# Versie_4.net
KiCad netlist of a schematic drawn in EAGLE
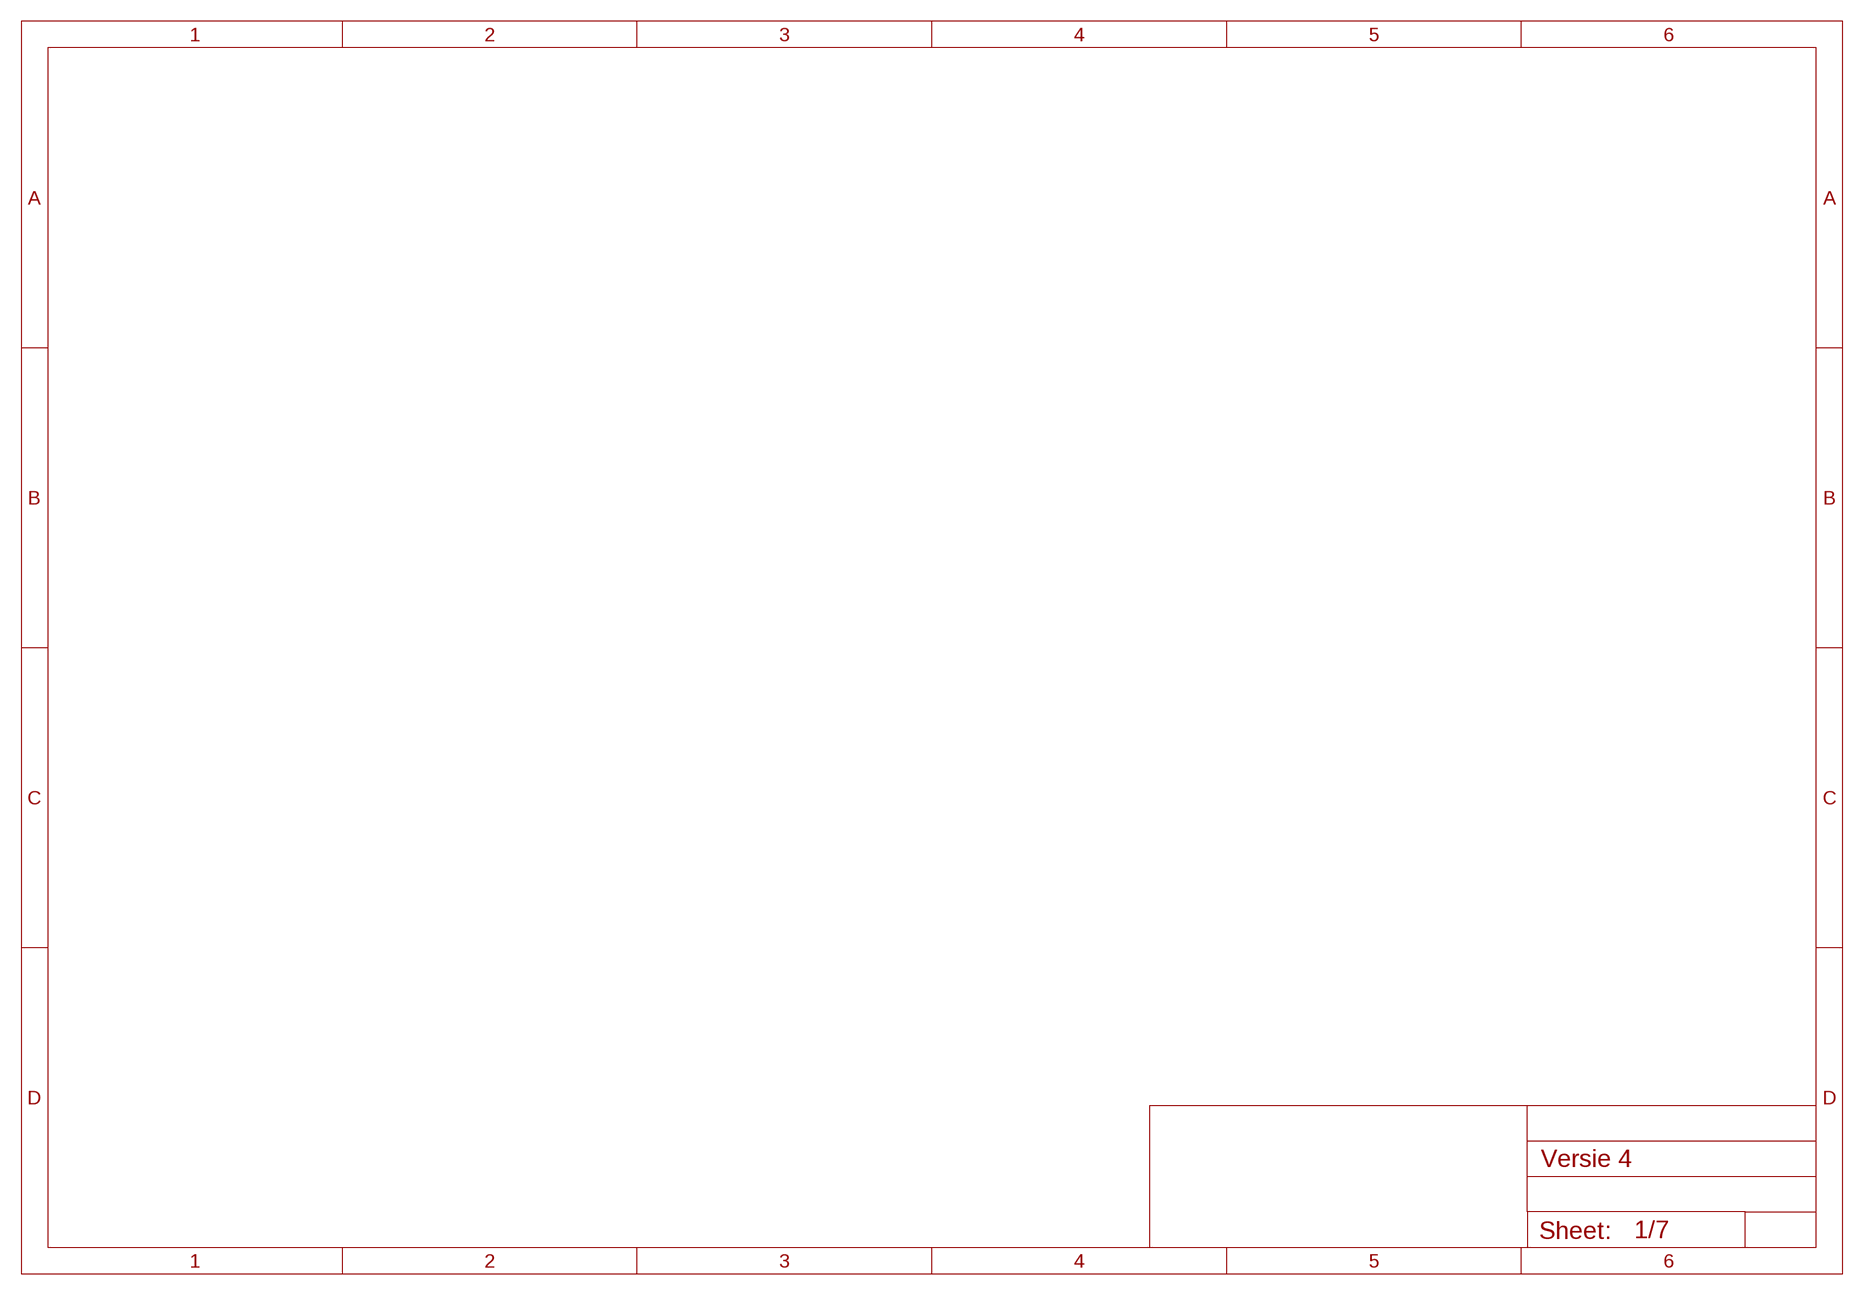
[diagram p0: schematic, sheet 1]
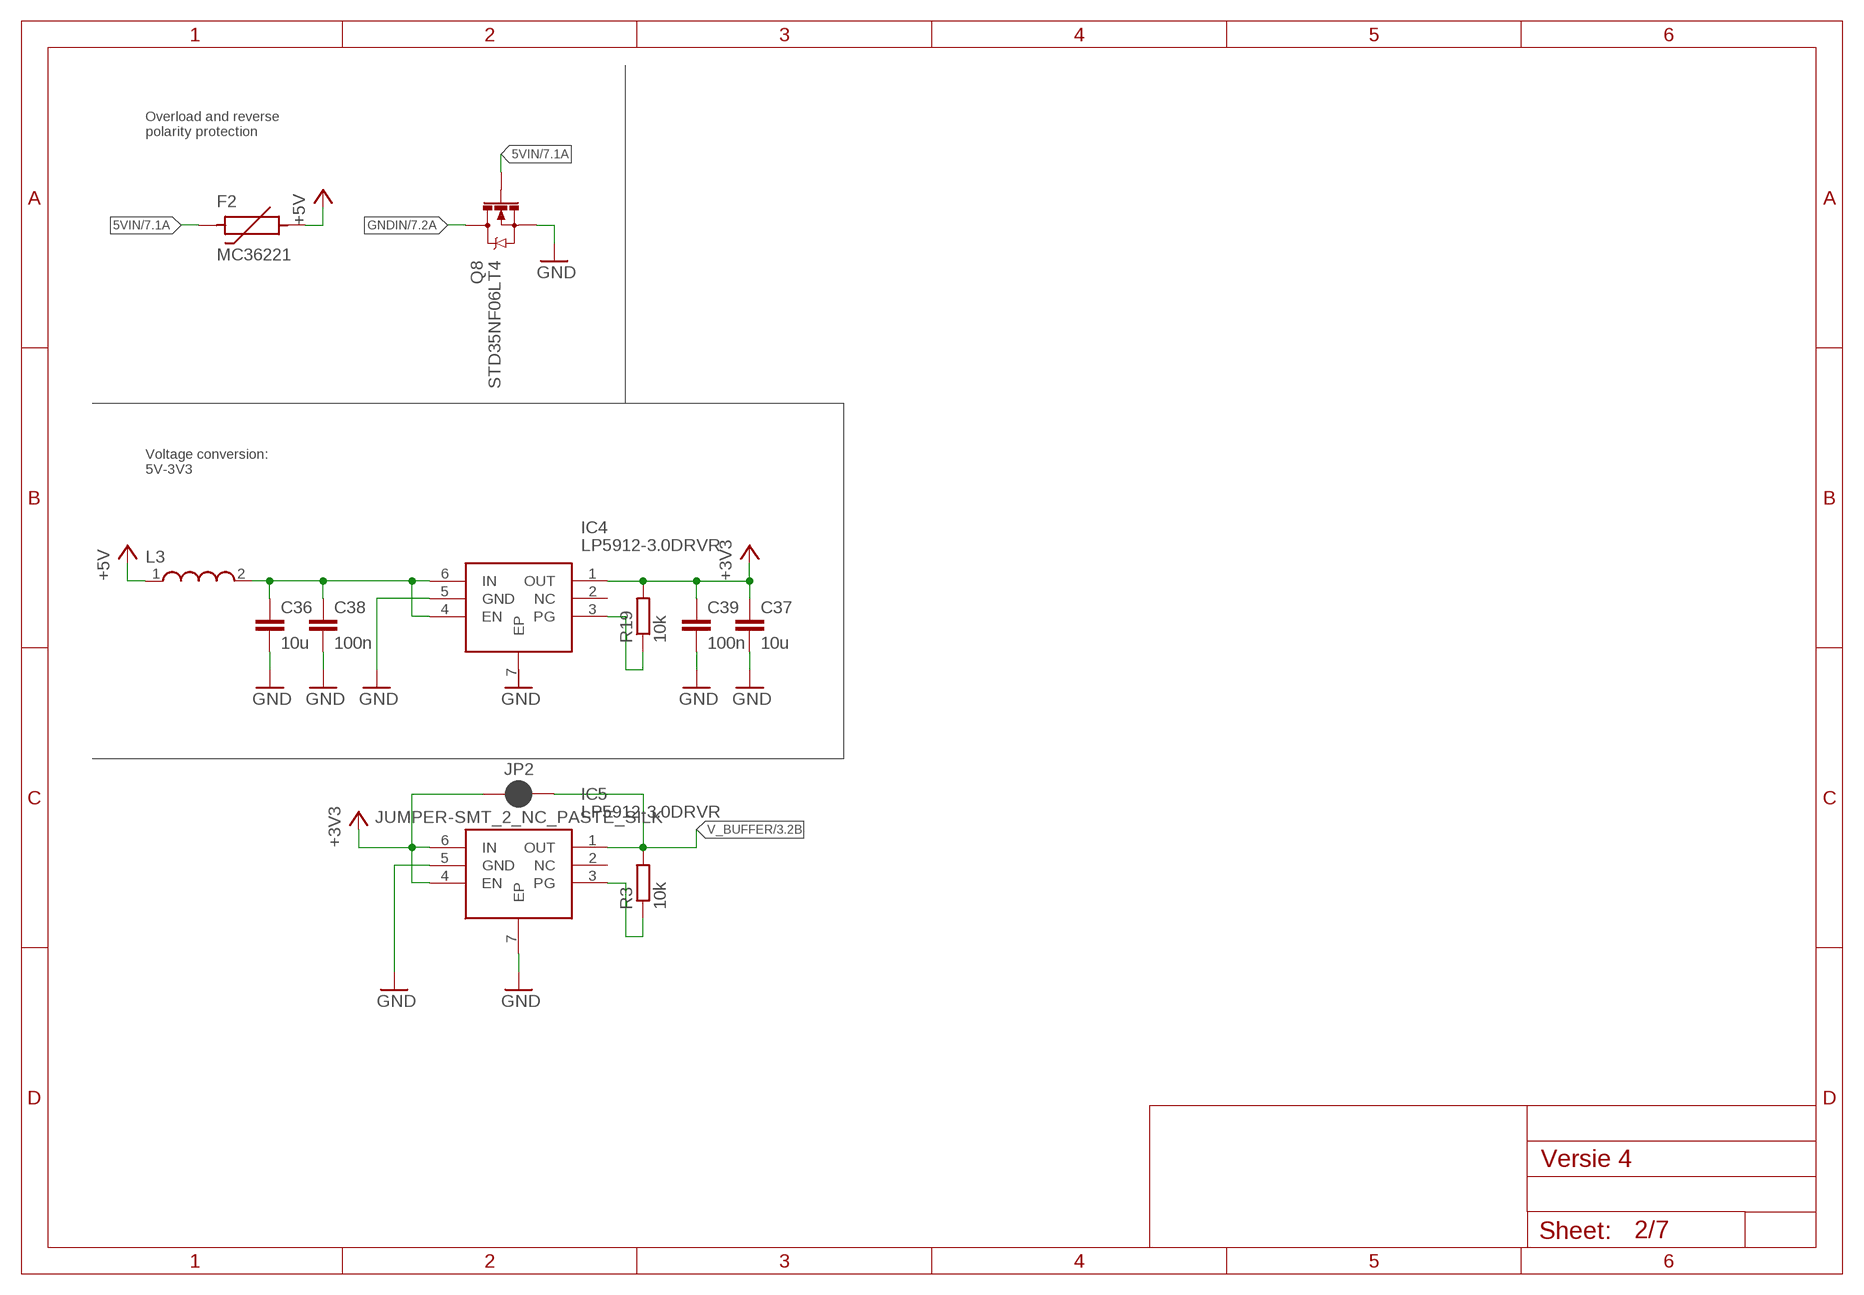
[diagram p1: schematic, sheet 2]
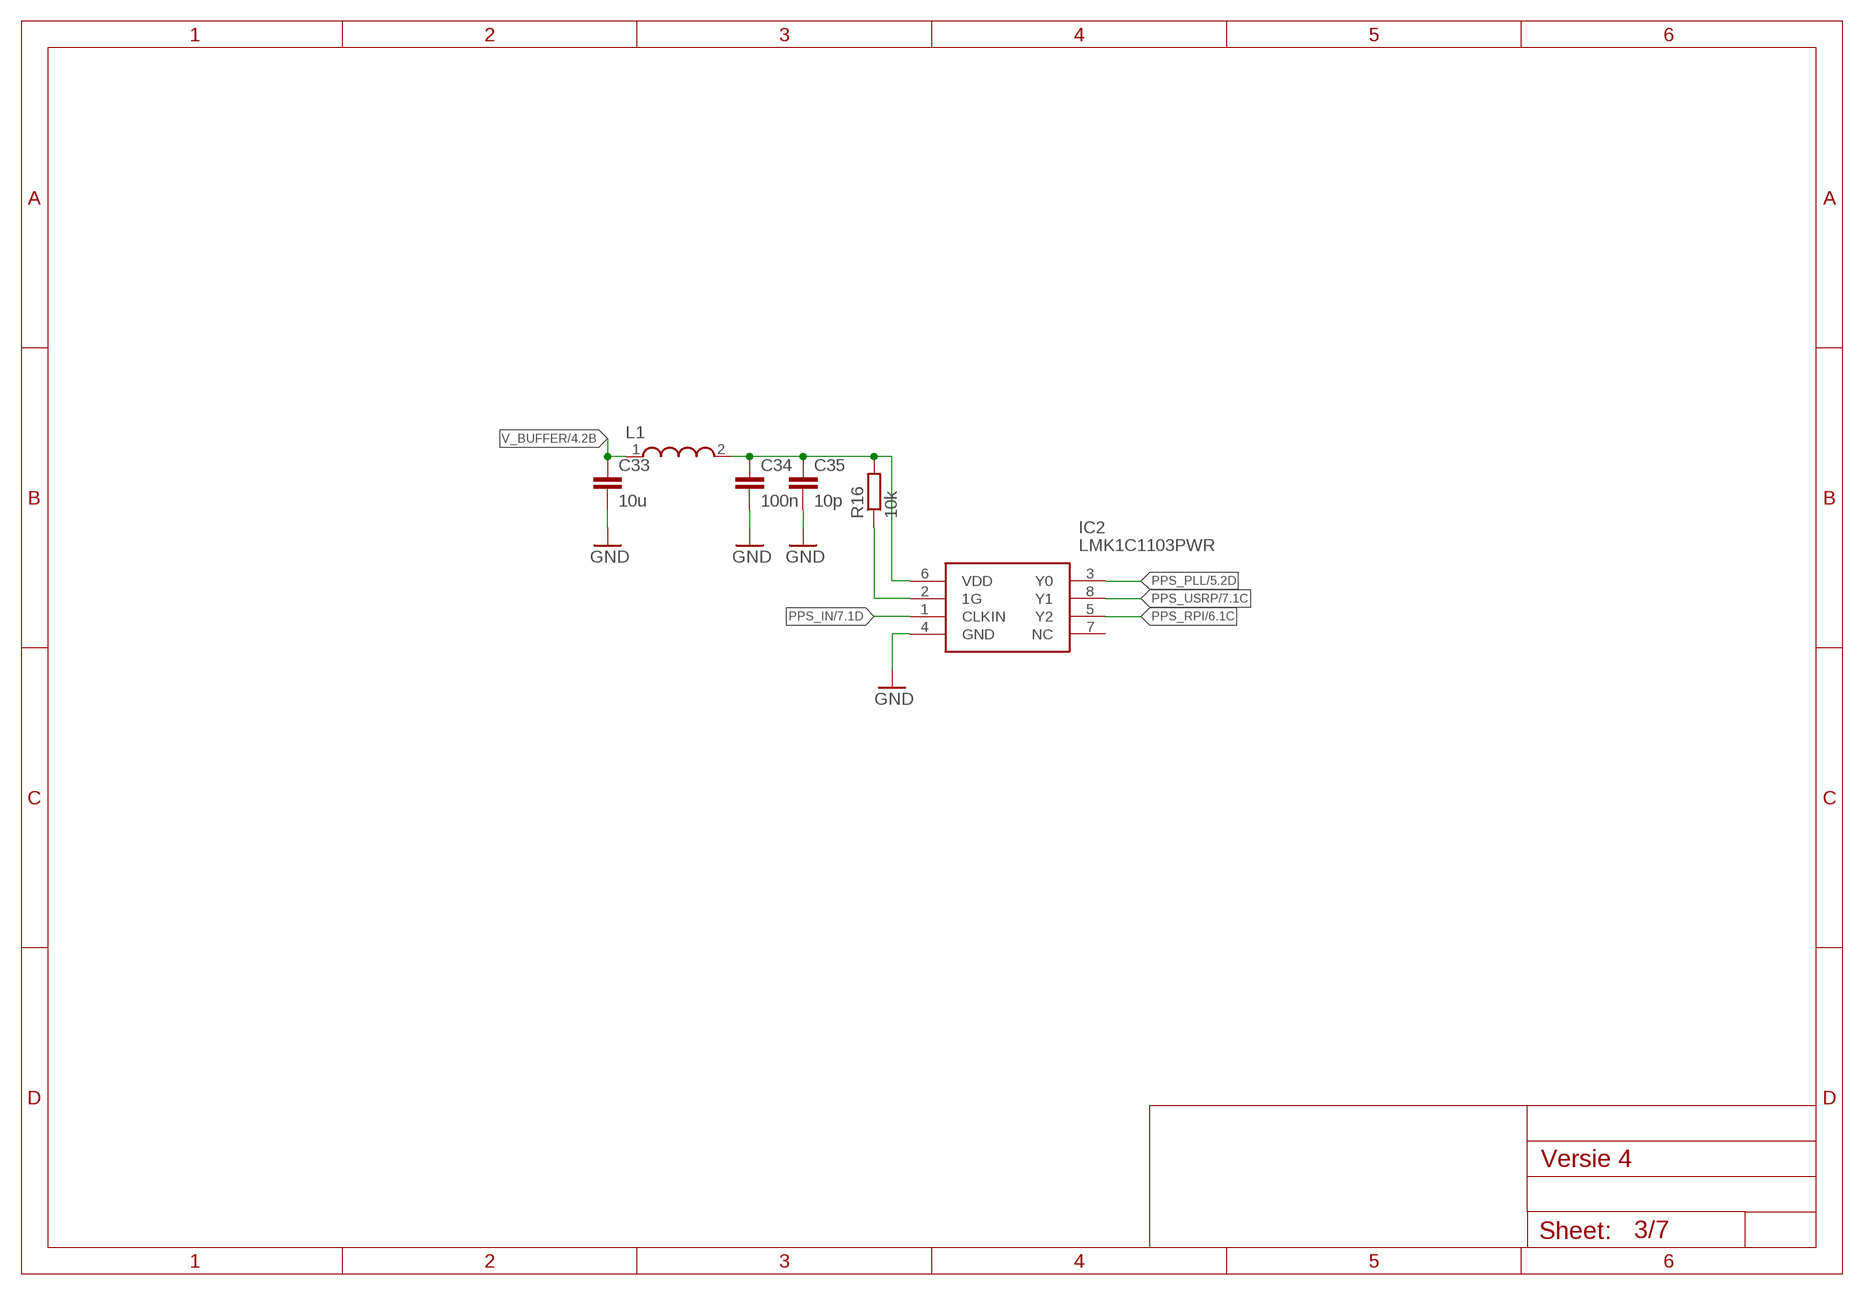
[diagram p2: schematic, sheet 3]
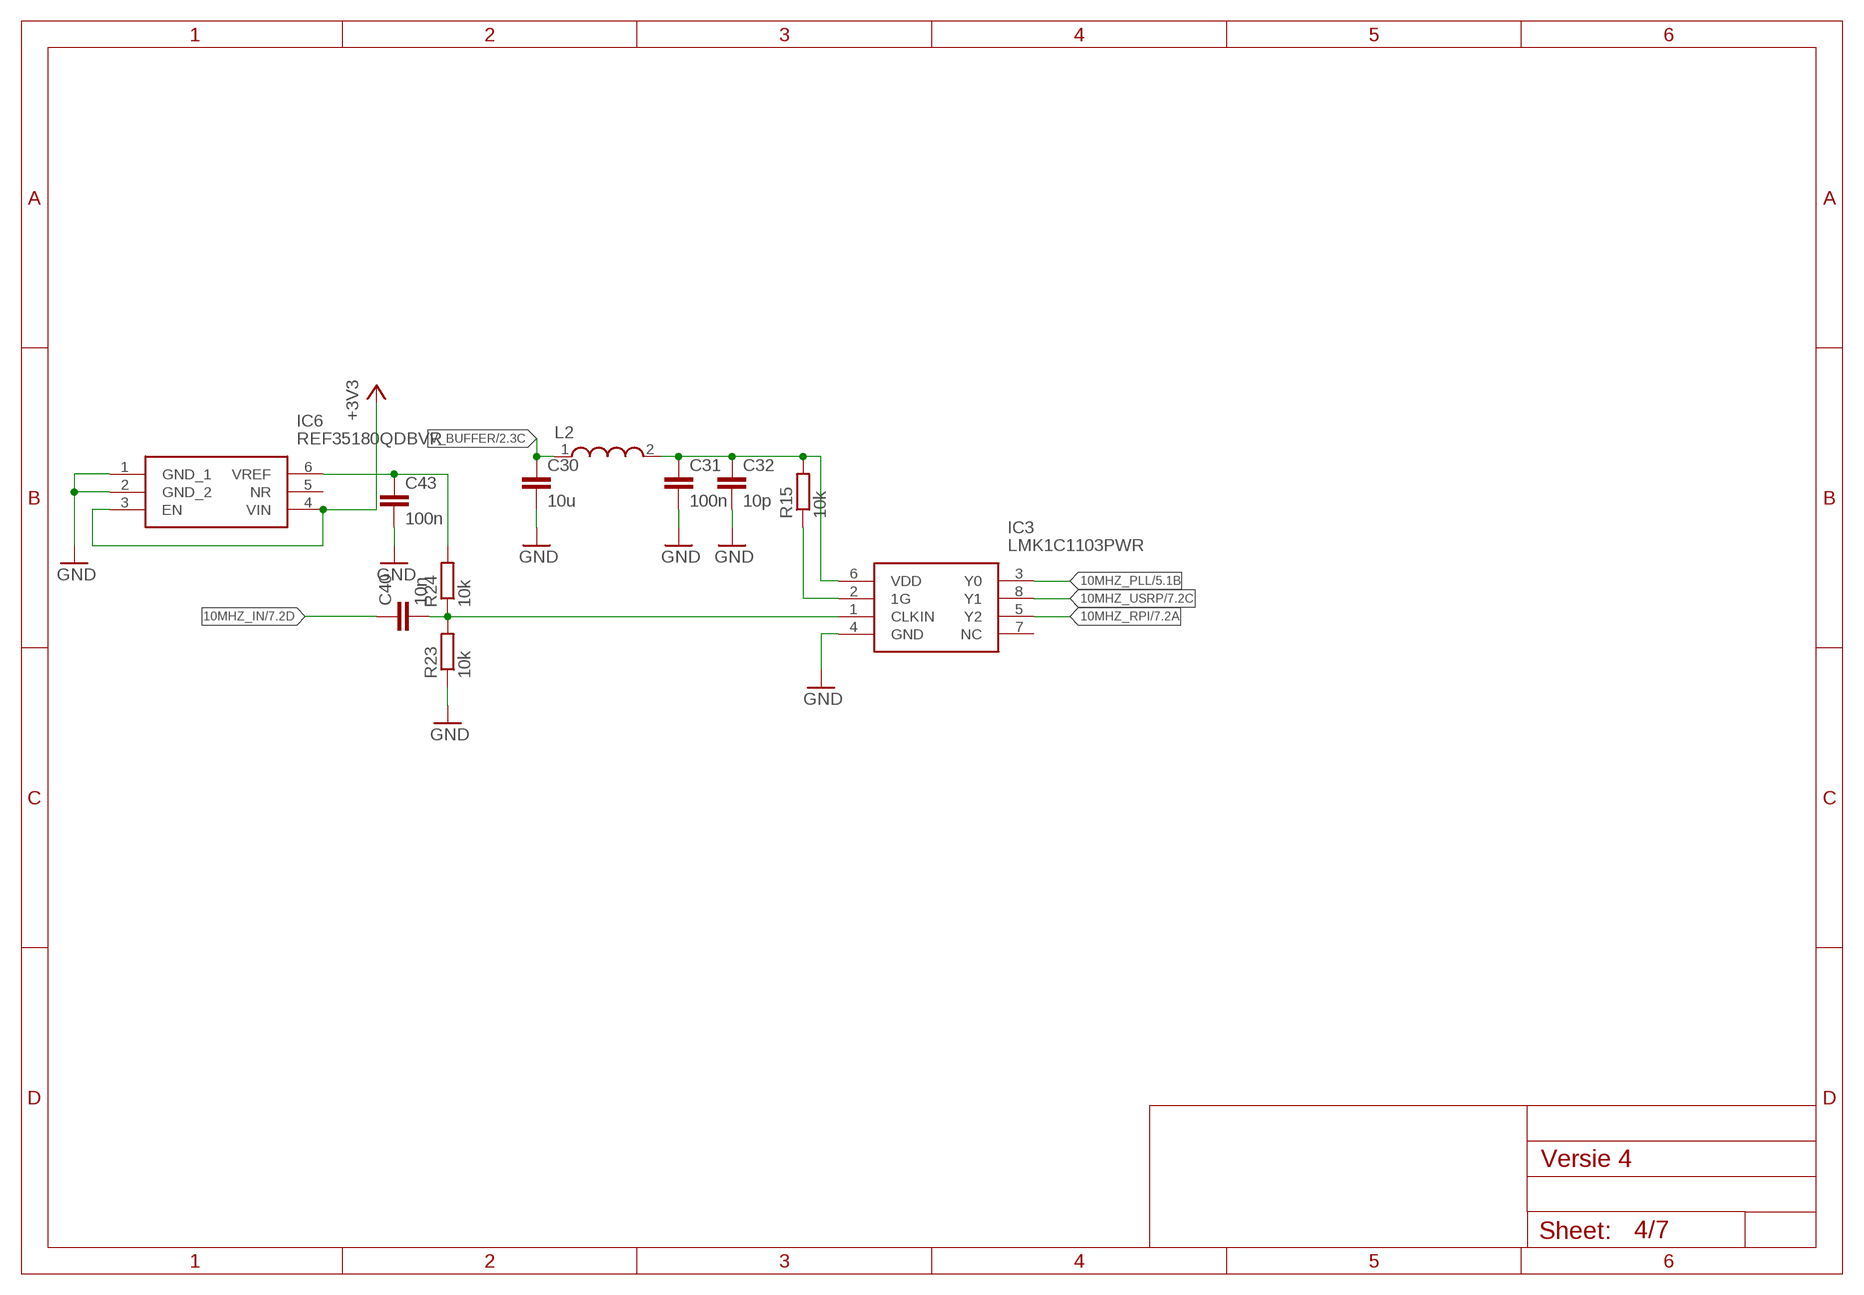
[diagram p3: schematic, sheet 4]
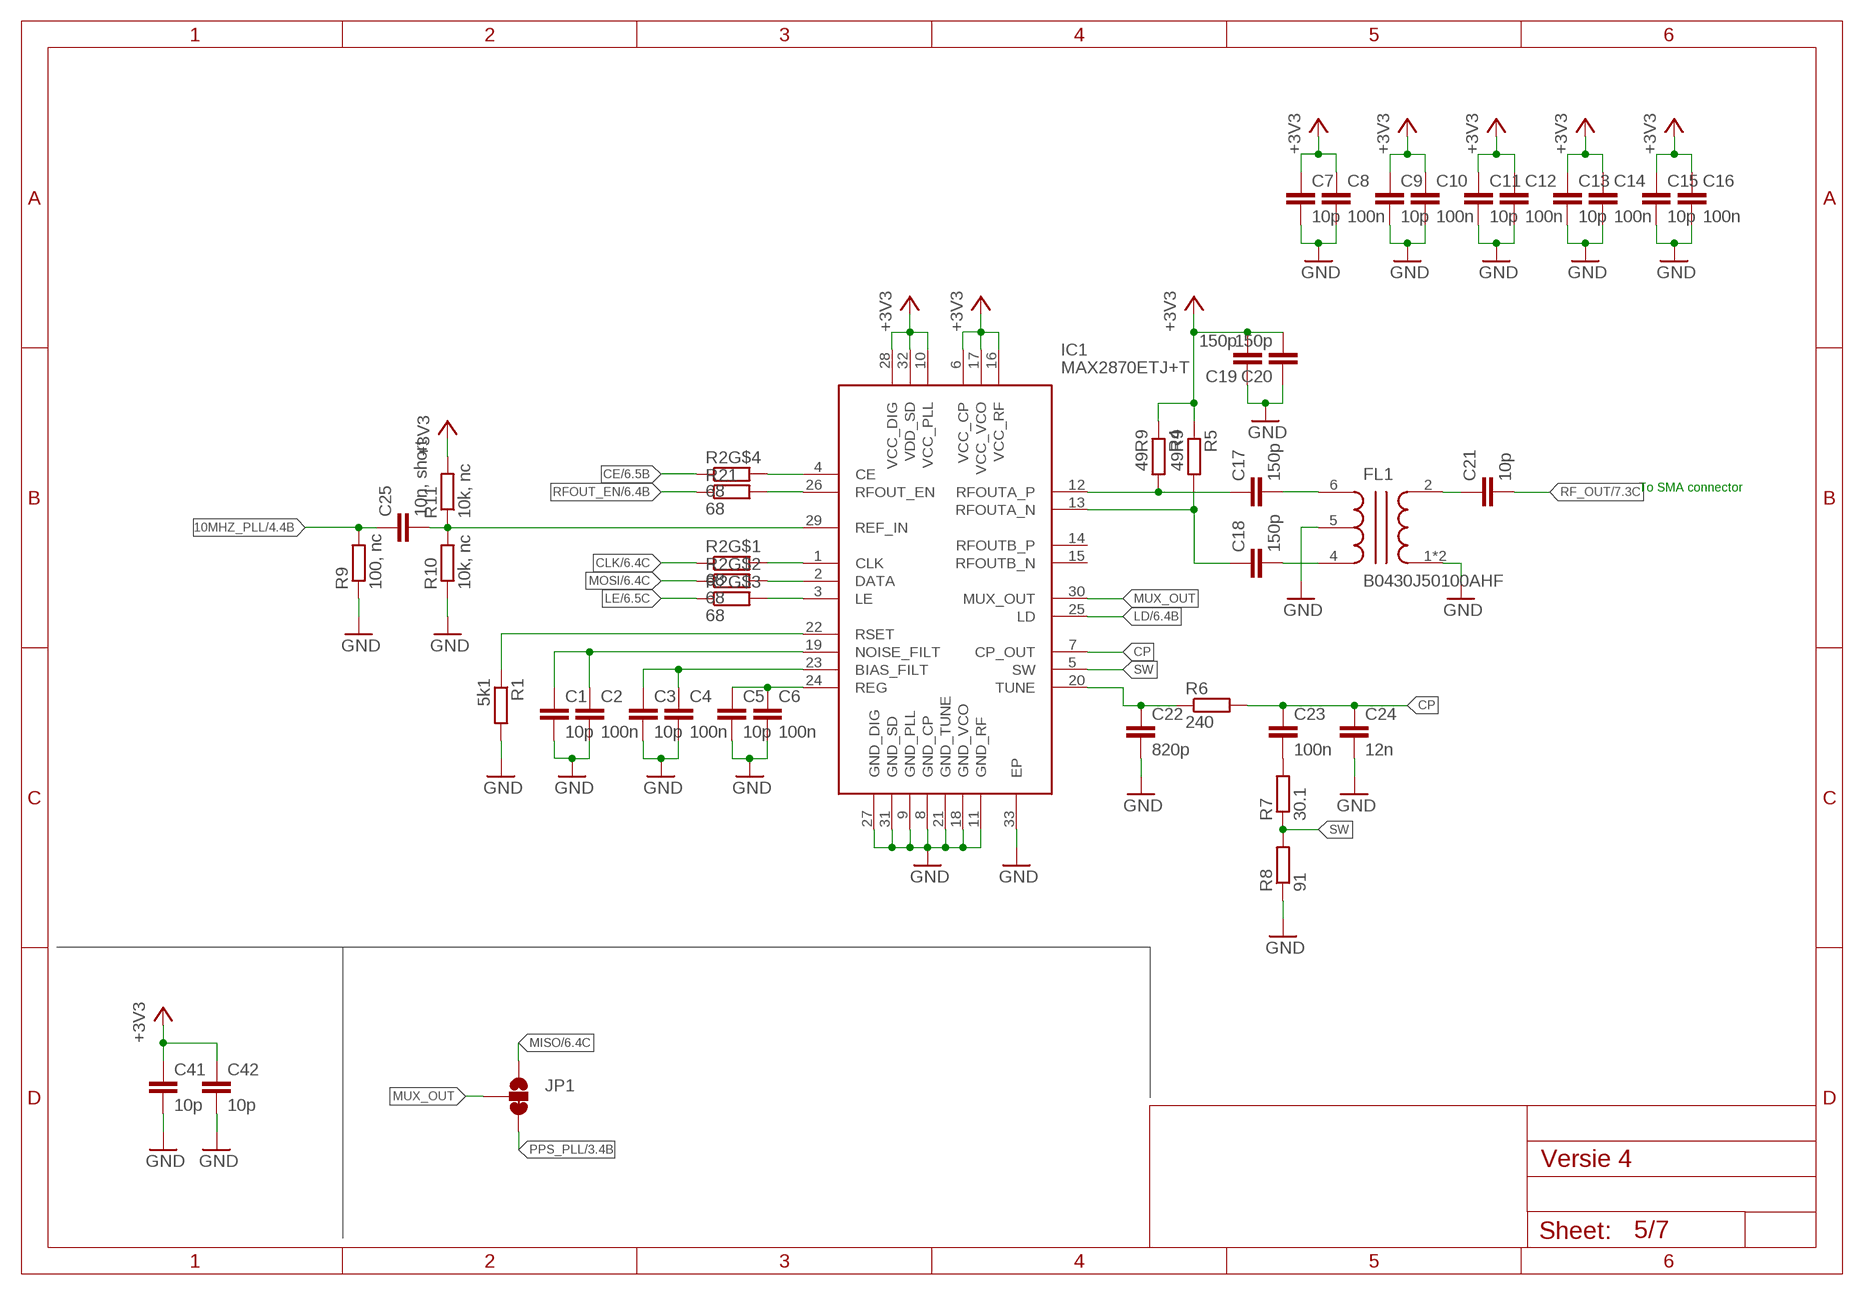
[diagram p4: schematic, sheet 5]
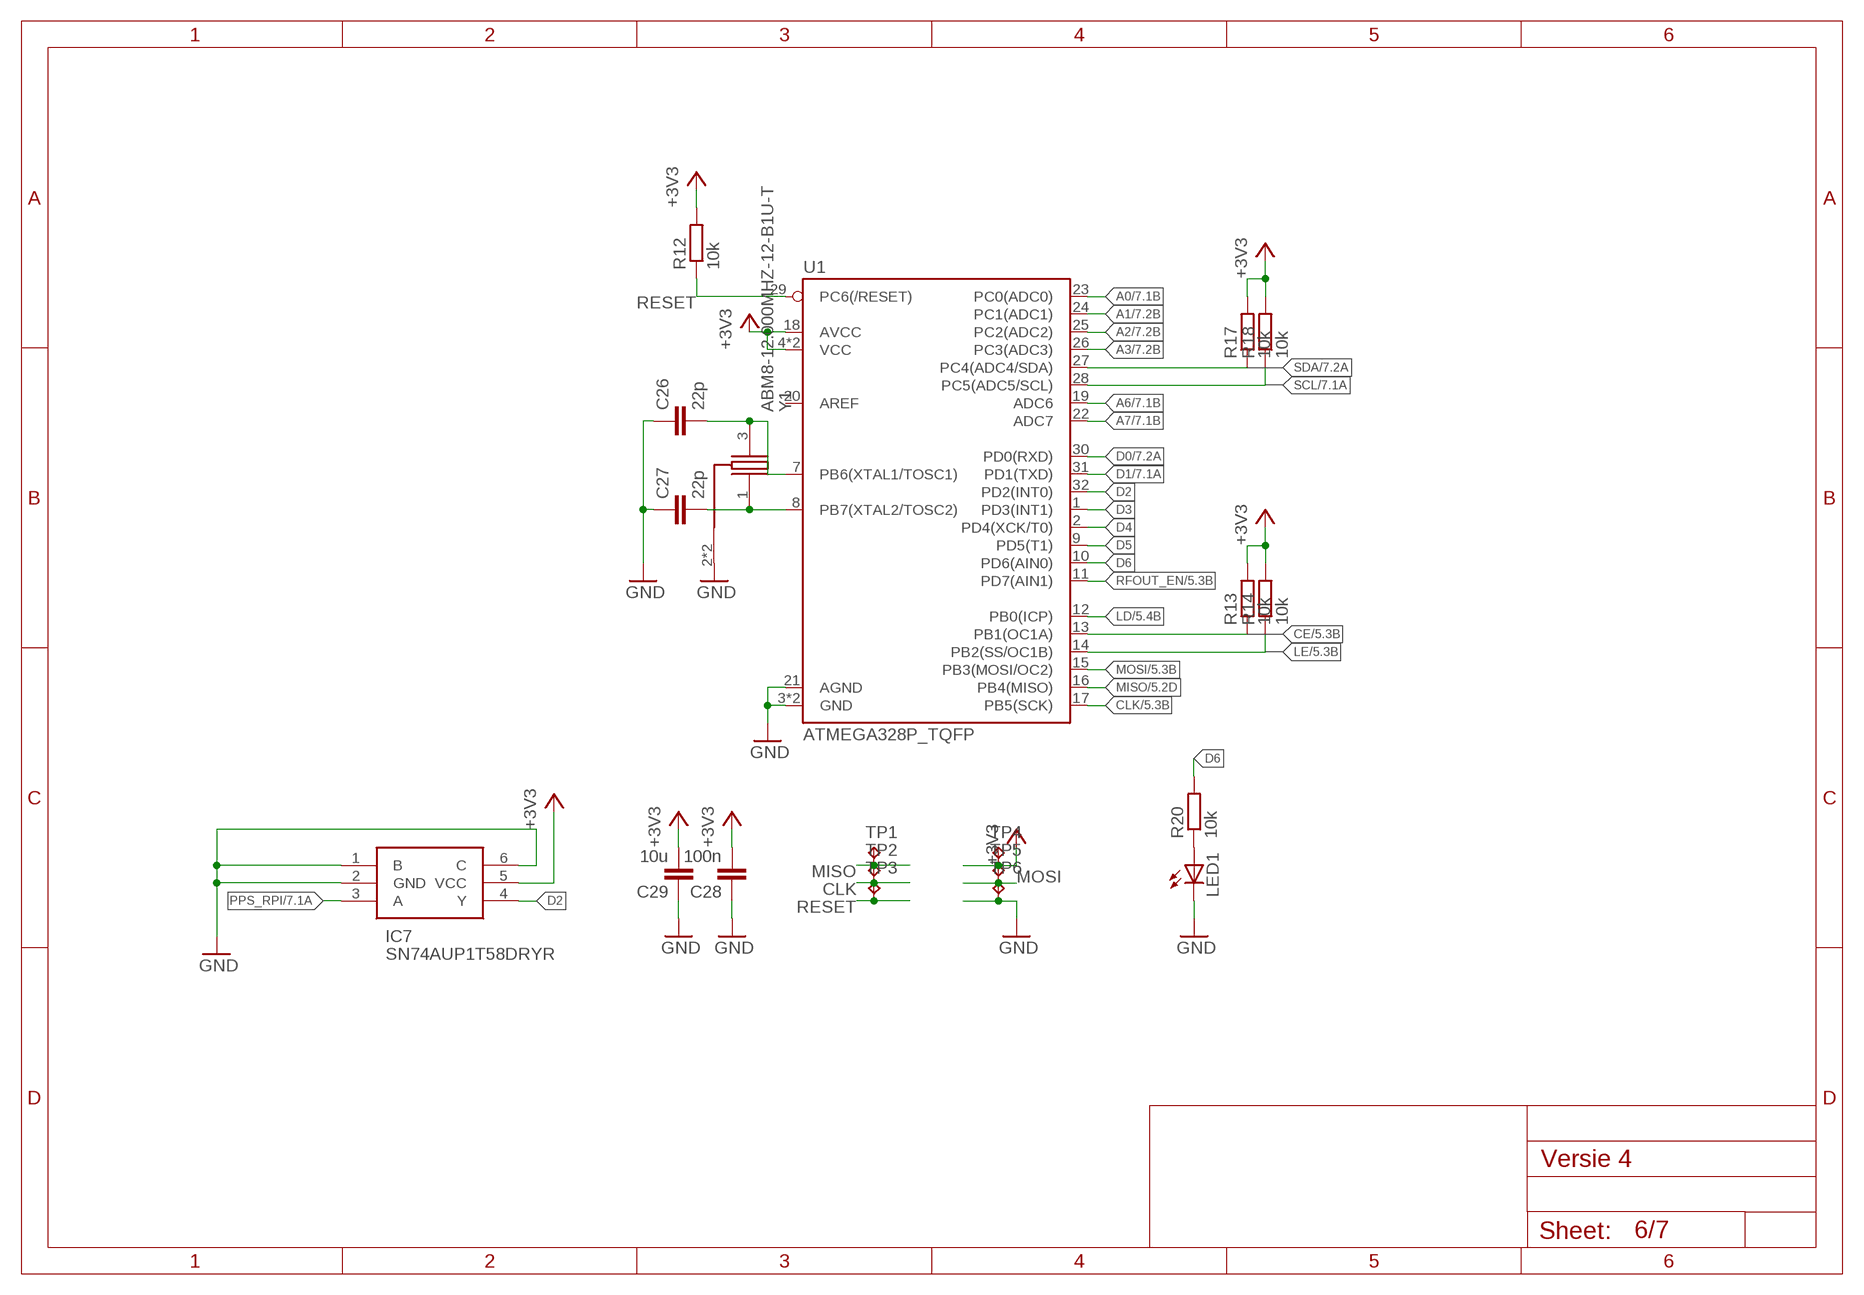
[diagram p5: schematic, sheet 6]
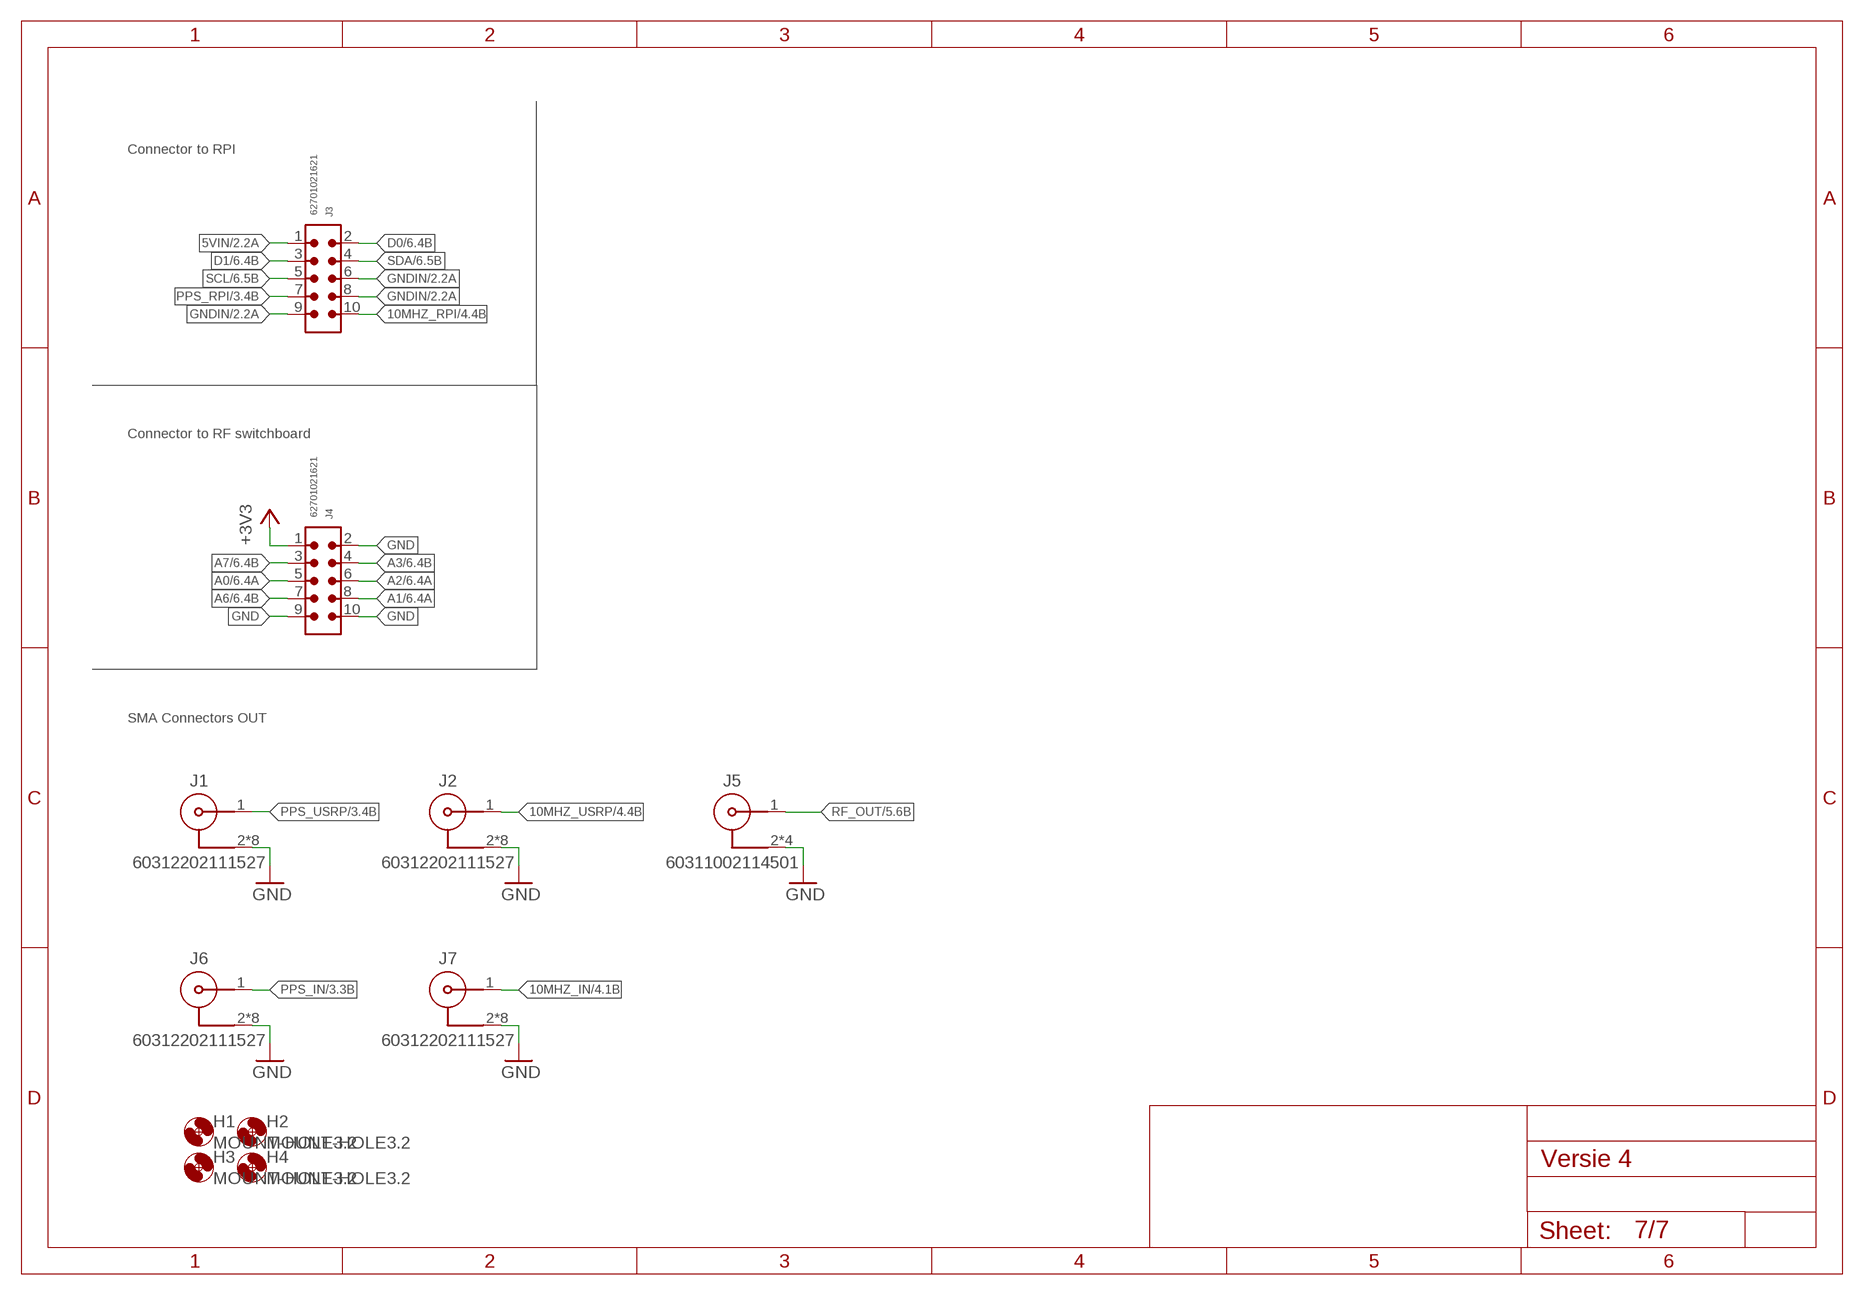
[diagram p6: schematic, sheet 7]

(export (version "E")
  (design (tool "Eeschema 10.0.6"))
  (components
    (comp (ref "C1")
      (value "10p")
      (footprint "eagle-import:C0603")
      (libsource (lib "eagle-import") (part "C-EUC0603"))
    )
    (comp (ref "C2")
      (value "100n")
      (footprint "eagle-import:C0603")
      (libsource (lib "eagle-import") (part "C-EUC0603"))
    )
    (comp (ref "C3")
      (value "10p")
      (footprint "eagle-import:C0603")
      (libsource (lib "eagle-import") (part "C-EUC0603"))
    )
    (comp (ref "C4")
      (value "100n")
      (footprint "eagle-import:C0603")
      (libsource (lib "eagle-import") (part "C-EUC0603"))
    )
    (comp (ref "C5")
      (value "10p")
      (footprint "eagle-import:C0603")
      (libsource (lib "eagle-import") (part "C-EUC0603"))
    )
    (comp (ref "C6")
      (value "100n")
      (footprint "eagle-import:C0603")
      (libsource (lib "eagle-import") (part "C-EUC0603"))
    )
    (comp (ref "C7")
      (value "10p")
      (footprint "eagle-import:C0603")
      (libsource (lib "eagle-import") (part "C-EUC0603"))
    )
    (comp (ref "C8")
      (value "100n")
      (footprint "eagle-import:C0603")
      (libsource (lib "eagle-import") (part "C-EUC0603"))
    )
    (comp (ref "C9")
      (value "10p")
      (footprint "eagle-import:C0603")
      (libsource (lib "eagle-import") (part "C-EUC0603"))
    )
    (comp (ref "C10")
      (value "100n")
      (footprint "eagle-import:C0603")
      (libsource (lib "eagle-import") (part "C-EUC0603"))
    )
    (comp (ref "C11")
      (value "10p")
      (footprint "eagle-import:C0603")
      (libsource (lib "eagle-import") (part "C-EUC0603"))
    )
    (comp (ref "C12")
      (value "100n")
      (footprint "eagle-import:C0603")
      (libsource (lib "eagle-import") (part "C-EUC0603"))
    )
    (comp (ref "C13")
      (value "10p")
      (footprint "eagle-import:C0603")
      (libsource (lib "eagle-import") (part "C-EUC0603"))
    )
    (comp (ref "C14")
      (value "100n")
      (footprint "eagle-import:C0603")
      (libsource (lib "eagle-import") (part "C-EUC0603"))
    )
    (comp (ref "C15")
      (value "10p")
      (footprint "eagle-import:C0603")
      (libsource (lib "eagle-import") (part "C-EUC0603"))
    )
    (comp (ref "C16")
      (value "100n")
      (footprint "eagle-import:C0603")
      (libsource (lib "eagle-import") (part "C-EUC0603"))
    )
    (comp (ref "C17")
      (value "150p")
      (footprint "eagle-import:C0402")
      (libsource (lib "eagle-import") (part "C-EUC0402"))
    )
    (comp (ref "C18")
      (value "150p")
      (footprint "eagle-import:C0402")
      (libsource (lib "eagle-import") (part "C-EUC0402"))
    )
    (comp (ref "C19")
      (value "150p")
      (footprint "eagle-import:C0402")
      (libsource (lib "eagle-import") (part "C-EUC0402"))
    )
    (comp (ref "C20")
      (value "150p")
      (footprint "eagle-import:C0402")
      (libsource (lib "eagle-import") (part "C-EUC0402"))
    )
    (comp (ref "C21")
      (value "10p")
      (footprint "eagle-import:C0402")
      (libsource (lib "eagle-import") (part "C-EUC0402"))
    )
    (comp (ref "C22")
      (value "820p")
      (footprint "eagle-import:C0603")
      (libsource (lib "eagle-import") (part "C-EUC0603"))
    )
    (comp (ref "C23")
      (value "100n")
      (footprint "eagle-import:C0603")
      (libsource (lib "eagle-import") (part "C-EUC0603"))
    )
    (comp (ref "C24")
      (value "12n")
      (footprint "eagle-import:C0603")
      (libsource (lib "eagle-import") (part "C-EUC0603"))
    )
    (comp (ref "C25")
      (value "10n, short")
      (footprint "eagle-import:C0603")
      (libsource (lib "eagle-import") (part "C-EUC0603"))
    )
    (comp (ref "C41")
      (value "10p")
      (footprint "eagle-import:C0603")
      (libsource (lib "eagle-import") (part "C-EUC0603"))
    )
    (comp (ref "C42")
      (value "10p")
      (footprint "eagle-import:C0603")
      (libsource (lib "eagle-import") (part "C-EUC0603"))
    )
    (comp (ref "FL1")
      (value "B0430J50100AHF")
      (footprint "eagle-import:B0430J50100AHF")
      (fields (field (name "MOUSER_PART_NUMBER") "620-B0430J50100AHF"))
      (libsource (lib "eagle-import") (part "B0430J50100AHF"))
    )
    (comp (ref "IC1")
      (value "MAX2870ETJ+T")
      (footprint "eagle-import:QFN50P500X500X80-33N")
      (fields (field (name "MOUSER_PART_NUMBER") "700-MAX2870ETJ+T"))
      (libsource (lib "eagle-import") (part "MAX2870ETJ+T"))
    )
    (comp (ref "JP1")
      (value "JUMPER-SMT_3_1-NC_TRACE_SILK")
      (footprint "eagle-import:SMT-JUMPER_3_1-NC_TRACE_SILK")
      (libsource (lib "eagle-import") (part "JUMPER-SMT_3_1-NC_TRACE_SILK"))
    )
    (comp (ref "R1")
      (value "5k1")
      (footprint "eagle-import:R0603")
      (libsource (lib "eagle-import") (part "R-EU_R0603"))
    )
    (comp (ref "R2")
      (value "68")
      (footprint "eagle-import:CAY16A1003F4LF")
      (fields
        (field (name "MANUFACTURER_PART_NUMBER") "CAY16A-2002F4LF")
        (field (name "MOUSER_PART_NUMBER") "652-CAY16A-2002F4LF")
      )
      (libsource (lib "eagle-import") (part "CAY16A-2002F4LF"))
    )
    (comp (ref "R4")
      (value "49R9")
      (footprint "eagle-import:R0402")
      (libsource (lib "eagle-import") (part "R-EU_R0402"))
    )
    (comp (ref "R5")
      (value "49R9")
      (footprint "eagle-import:R0402")
      (libsource (lib "eagle-import") (part "R-EU_R0402"))
    )
    (comp (ref "R6")
      (value "240")
      (footprint "eagle-import:R0603")
      (libsource (lib "eagle-import") (part "R-EU_R0603"))
    )
    (comp (ref "R7")
      (value "30.1")
      (footprint "eagle-import:R0603")
      (libsource (lib "eagle-import") (part "R-EU_R0603"))
    )
    (comp (ref "R8")
      (value "91")
      (footprint "eagle-import:R0603")
      (libsource (lib "eagle-import") (part "R-EU_R0603"))
    )
    (comp (ref "R9")
      (value "100, nc")
      (footprint "eagle-import:R0603")
      (libsource (lib "eagle-import") (part "R-EU_R0603"))
    )
    (comp (ref "R10")
      (value "10k, nc")
      (footprint "eagle-import:R0603")
      (libsource (lib "eagle-import") (part "R-EU_R0603"))
    )
    (comp (ref "R11")
      (value "10k, nc")
      (footprint "eagle-import:R0603")
      (libsource (lib "eagle-import") (part "R-EU_R0603"))
    )
    (comp (ref "R21")
      (value "68")
      (footprint "eagle-import:R0603")
      (libsource (lib "eagle-import") (part "R-EU_R0603"))
    )
    (comp (ref "H1")
      (value "MOUNT-HOLE3.2")
      (footprint "eagle-import:3,2")
      (libsource (lib "eagle-import") (part "MOUNT-HOLE3.2"))
    )
    (comp (ref "H2")
      (value "MOUNT-HOLE3.2")
      (footprint "eagle-import:3,2")
      (libsource (lib "eagle-import") (part "MOUNT-HOLE3.2"))
    )
    (comp (ref "H3")
      (value "MOUNT-HOLE3.2")
      (footprint "eagle-import:3,2")
      (libsource (lib "eagle-import") (part "MOUNT-HOLE3.2"))
    )
    (comp (ref "H4")
      (value "MOUNT-HOLE3.2")
      (footprint "eagle-import:3,2")
      (libsource (lib "eagle-import") (part "MOUNT-HOLE3.2"))
    )
    (comp (ref "J1")
      (value "60312202111527")
      (footprint "eagle-import:60312202111527")
      (libsource (lib "eagle-import") (part "60312202111527"))
    )
    (comp (ref "J2")
      (value "60312202111527")
      (footprint "eagle-import:60312202111527")
      (libsource (lib "eagle-import") (part "60312202111527"))
    )
    (comp (ref "J3")
      (value "62701021621")
      (footprint "eagle-import:62701021621")
      (libsource (lib "eagle-import") (part "6270XX21621_62701021621"))
    )
    (comp (ref "J4")
      (value "62701021621")
      (footprint "eagle-import:62701021621")
      (libsource (lib "eagle-import") (part "6270XX21621_62701021621"))
    )
    (comp (ref "J5")
      (value "60311002114501")
      (footprint "eagle-import:60311002114501")
      (libsource (lib "eagle-import") (part "60311002114501"))
    )
    (comp (ref "J6")
      (value "60312202111527")
      (footprint "eagle-import:60312202111527")
      (libsource (lib "eagle-import") (part "60312202111527"))
    )
    (comp (ref "J7")
      (value "60312202111527")
      (footprint "eagle-import:60312202111527")
      (libsource (lib "eagle-import") (part "60312202111527"))
    )
    (comp (ref "C36")
      (value "10u")
      (footprint "eagle-import:C0603")
      (libsource (lib "eagle-import") (part "C-EUC0603"))
    )
    (comp (ref "C37")
      (value "10u")
      (footprint "eagle-import:C0603")
      (libsource (lib "eagle-import") (part "C-EUC0603"))
    )
    (comp (ref "C38")
      (value "100n")
      (footprint "eagle-import:C0603")
      (libsource (lib "eagle-import") (part "C-EUC0603"))
    )
    (comp (ref "C39")
      (value "100n")
      (footprint "eagle-import:C0603")
      (libsource (lib "eagle-import") (part "C-EUC0603"))
    )
    (comp (ref "F2")
      (value "MC36221")
      (footprint "eagle-import:1206")
      (libsource (lib "eagle-import") (part "MC36221"))
    )
    (comp (ref "IC4")
      (value "LP5912-3.0DRVR")
      (footprint "eagle-import:SON65P200X200X80-7N")
      (fields (field (name "MOUSER_PART_NUMBER") "595-LP5912-3.0DRVR"))
      (libsource (lib "eagle-import") (part "LP5912-3.0DRVR"))
    )
    (comp (ref "IC5")
      (value "LP5912-3.0DRVR")
      (footprint "eagle-import:SON65P200X200X80-7N")
      (fields (field (name "MOUSER_PART_NUMBER") "595-LP5912-3.0DRVR"))
      (libsource (lib "eagle-import") (part "LP5912-3.0DRVR"))
    )
    (comp (ref "JP2")
      (value "JUMPER-SMT_2_NC_PASTE_SILK")
      (footprint "eagle-import:SMT-JUMPER_2_NC_PASTE_SILK")
      (libsource (lib "eagle-import") (part "JUMPER-SMT_2_NC_PASTE_SILK"))
    )
    (comp (ref "L3")
      (value "WE-CBA_0603(WB/HS)")
      (footprint "eagle-import:WE-CBA_0603(W=2.2)")
      (libsource (lib "eagle-import") (part "WE-CBA_0603(WB/HS)"))
    )
    (comp (ref "Q8")
      (value "STD35NF06LT4")
      (footprint "eagle-import:SOT23-3")
      (libsource (lib "eagle-import") (part "MOSFET-NCHANNEL_SOT23-3"))
    )
    (comp (ref "R3")
      (value "10k")
      (footprint "eagle-import:R0603")
      (libsource (lib "eagle-import") (part "R-EU_R0603"))
    )
    (comp (ref "R19")
      (value "10k")
      (footprint "eagle-import:R0603")
      (libsource (lib "eagle-import") (part "R-EU_R0603"))
    )
    (comp (ref "C33")
      (value "10u")
      (footprint "eagle-import:C0603")
      (libsource (lib "eagle-import") (part "C-EUC0603"))
    )
    (comp (ref "C34")
      (value "100n")
      (footprint "eagle-import:C0603")
      (libsource (lib "eagle-import") (part "C-EUC0603"))
    )
    (comp (ref "C35")
      (value "10p")
      (footprint "eagle-import:C0603")
      (libsource (lib "eagle-import") (part "C-EUC0603"))
    )
    (comp (ref "IC2")
      (value "LMK1C1103PWR")
      (footprint "eagle-import:SOP65P640X120-8N")
      (fields (field (name "MOUSER_PART_NUMBER") "595-LMK1C1103PWR"))
      (libsource (lib "eagle-import") (part "LMK1C1103PWR"))
    )
    (comp (ref "L1")
      (value "WE-CBA_0603(WB/HS)")
      (footprint "eagle-import:WE-CBA_0603(W=2.2)")
      (libsource (lib "eagle-import") (part "WE-CBA_0603(WB/HS)"))
    )
    (comp (ref "R16")
      (value "10k")
      (footprint "eagle-import:R0603")
      (libsource (lib "eagle-import") (part "R-EU_R0603"))
    )
    (comp (ref "C26")
      (value "22p")
      (footprint "eagle-import:C0603")
      (libsource (lib "eagle-import") (part "C-EUC0603"))
    )
    (comp (ref "C27")
      (value "22p")
      (footprint "eagle-import:C0603")
      (libsource (lib "eagle-import") (part "C-EUC0603"))
    )
    (comp (ref "C28")
      (value "100n")
      (footprint "eagle-import:C0603")
      (libsource (lib "eagle-import") (part "C-EUC0603"))
    )
    (comp (ref "C29")
      (value "10u")
      (footprint "eagle-import:C0603")
      (libsource (lib "eagle-import") (part "C-EUC0603"))
    )
    (comp (ref "IC7")
      (value "SN74AUP1T58DRYR")
      (footprint "eagle-import:SON50P100X145X60-6N")
      (libsource (lib "eagle-import") (part "SN74AUP1T58DRYR"))
    )
    (comp (ref "LED1")
      (value "LEDCHIPLED_0603")
      (footprint "eagle-import:CHIPLED_0603")
      (libsource (lib "eagle-import") (part "LEDCHIPLED_0603"))
    )
    (comp (ref "R12")
      (value "10k")
      (footprint "eagle-import:R0603")
      (libsource (lib "eagle-import") (part "R-EU_R0603"))
    )
    (comp (ref "R13")
      (value "10k")
      (footprint "eagle-import:R0603")
      (libsource (lib "eagle-import") (part "R-EU_R0603"))
    )
    (comp (ref "R14")
      (value "10k")
      (footprint "eagle-import:R0603")
      (libsource (lib "eagle-import") (part "R-EU_R0603"))
    )
    (comp (ref "R17")
      (value "10k")
      (footprint "eagle-import:R0603")
      (libsource (lib "eagle-import") (part "R-EU_R0603"))
    )
    (comp (ref "R18")
      (value "10k")
      (footprint "eagle-import:R0603")
      (libsource (lib "eagle-import") (part "R-EU_R0603"))
    )
    (comp (ref "R20")
      (value "10k")
      (footprint "eagle-import:R0603")
      (libsource (lib "eagle-import") (part "R-EU_R0603"))
    )
    (comp (ref "TP1")
      (value "TPTP16R")
      (footprint "eagle-import:TP16R")
      (libsource (lib "eagle-import") (part "TPTP16R"))
    )
    (comp (ref "TP2")
      (value "TPTP16R")
      (footprint "eagle-import:TP16R")
      (libsource (lib "eagle-import") (part "TPTP16R"))
    )
    (comp (ref "TP3")
      (value "TPTP16R")
      (footprint "eagle-import:TP16R")
      (libsource (lib "eagle-import") (part "TPTP16R"))
    )
    (comp (ref "TP4")
      (value "TPTP16R")
      (footprint "eagle-import:TP16R")
      (libsource (lib "eagle-import") (part "TPTP16R"))
    )
    (comp (ref "TP5")
      (value "TPTP16R")
      (footprint "eagle-import:TP16R")
      (libsource (lib "eagle-import") (part "TPTP16R"))
    )
    (comp (ref "TP6")
      (value "TPTP16R")
      (footprint "eagle-import:TP16R")
      (libsource (lib "eagle-import") (part "TPTP16R"))
    )
    (comp (ref "U1")
      (value "ATMEGA328P_TQFP")
      (footprint "eagle-import:TQFP32-08")
      (libsource (lib "eagle-import") (part "ATMEGA328P_TQFP"))
    )
    (comp (ref "Y1")
      (value "ABM8-12.000MHZ-12-B1U-T")
      (footprint "eagle-import:ABM810000MHZ12D2W")
      (fields (field (name "MOUSER_PART_NUMBER") "815-M812000MHZ12B1UT"))
      (libsource (lib "eagle-import") (part "ABM8-12.000MHZ-12-B1U-T"))
    )
    (comp (ref "C30")
      (value "10u")
      (footprint "eagle-import:C0603")
      (libsource (lib "eagle-import") (part "C-EUC0603"))
    )
    (comp (ref "C31")
      (value "100n")
      (footprint "eagle-import:C0603")
      (libsource (lib "eagle-import") (part "C-EUC0603"))
    )
    (comp (ref "C32")
      (value "10p")
      (footprint "eagle-import:C0603")
      (libsource (lib "eagle-import") (part "C-EUC0603"))
    )
    (comp (ref "C40")
      (value "10n")
      (footprint "eagle-import:C0603")
      (libsource (lib "eagle-import") (part "C-EUC0603"))
    )
    (comp (ref "C43")
      (value "100n")
      (footprint "eagle-import:C0603")
      (libsource (lib "eagle-import") (part "C-EUC0603"))
    )
    (comp (ref "IC3")
      (value "LMK1C1103PWR")
      (footprint "eagle-import:SOP65P640X120-8N")
      (fields (field (name "MOUSER_PART_NUMBER") "595-LMK1C1103PWR"))
      (libsource (lib "eagle-import") (part "LMK1C1103PWR"))
    )
    (comp (ref "IC6")
      (value "REF35180QDBVR")
      (footprint "eagle-import:SOT95P280X145-6N")
      (fields (field (name "MOUSER_PART_NUMBER") "595-REF35180QDBVR"))
      (libsource (lib "eagle-import") (part "REF35180QDBVR"))
    )
    (comp (ref "L2")
      (value "WE-CBA_0603(WB/HS)")
      (footprint "eagle-import:WE-CBA_0603(W=2.2)")
      (libsource (lib "eagle-import") (part "WE-CBA_0603(WB/HS)"))
    )
    (comp (ref "R15")
      (value "10k")
      (footprint "eagle-import:R0603")
      (libsource (lib "eagle-import") (part "R-EU_R0603"))
    )
    (comp (ref "R23")
      (value "10k")
      (footprint "eagle-import:R0603")
      (libsource (lib "eagle-import") (part "R-EU_R0603"))
    )
    (comp (ref "R24")
      (value "10k")
      (footprint "eagle-import:R0603")
      (libsource (lib "eagle-import") (part "R-EU_R0603"))
    )
  )
  (nets
    (net (code "1") (name "+3V3") (class "Default")
      (node (ref "C10") (pin "1") (pinfunction "1_1") (pintype "passive"))
      (node (ref "C11") (pin "1") (pinfunction "1_1") (pintype "passive"))
      (node (ref "C12") (pin "1") (pinfunction "1_1") (pintype "passive"))
      (node (ref "C13") (pin "1") (pinfunction "1_1") (pintype "passive"))
      (node (ref "C14") (pin "1") (pinfunction "1_1") (pintype "passive"))
      (node (ref "C15") (pin "1") (pinfunction "1_1") (pintype "passive"))
      (node (ref "C16") (pin "1") (pinfunction "1_1") (pintype "passive"))
      (node (ref "C19") (pin "2") (pinfunction "2_2") (pintype "passive"))
      (node (ref "C20") (pin "2") (pinfunction "2_2") (pintype "passive"))
      (node (ref "C28") (pin "2") (pinfunction "2_2") (pintype "passive"))
      (node (ref "C29") (pin "2") (pinfunction "2_2") (pintype "passive"))
      (node (ref "C37") (pin "1") (pinfunction "1_1") (pintype "passive"))
      (node (ref "C39") (pin "1") (pinfunction "1_1") (pintype "passive"))
      (node (ref "C41") (pin "1") (pinfunction "1_1") (pintype "passive"))
      (node (ref "C42") (pin "1") (pinfunction "1_1") (pintype "passive"))
      (node (ref "C7") (pin "1") (pinfunction "1_1") (pintype "passive"))
      (node (ref "C8") (pin "1") (pinfunction "1_1") (pintype "passive"))
      (node (ref "C9") (pin "1") (pinfunction "1_1") (pintype "passive"))
      (node (ref "IC1") (pin "10") (pinfunction "VCC_PLL_10") (pintype "bidirectional"))
      (node (ref "IC1") (pin "16") (pinfunction "VCC_RF_16") (pintype "bidirectional"))
      (node (ref "IC1") (pin "17") (pinfunction "VCC_VCO_17") (pintype "bidirectional"))
      (node (ref "IC1") (pin "28") (pinfunction "VCC_DIG_28") (pintype "bidirectional"))
      (node (ref "IC1") (pin "32") (pinfunction "VDD_SD_32") (pintype "bidirectional"))
      (node (ref "IC1") (pin "6") (pinfunction "VCC_CP_6") (pintype "bidirectional"))
      (node (ref "IC4") (pin "1") (pinfunction "OUT_1") (pintype "bidirectional"))
      (node (ref "IC5") (pin "4") (pinfunction "EN_4") (pintype "bidirectional"))
      (node (ref "IC5") (pin "6") (pinfunction "IN_6") (pintype "bidirectional"))
      (node (ref "IC6") (pin "3") (pinfunction "EN_3") (pintype "bidirectional"))
      (node (ref "IC6") (pin "4") (pinfunction "VIN_4") (pintype "bidirectional"))
      (node (ref "IC7") (pin "5") (pinfunction "VCC_5") (pintype "bidirectional"))
      (node (ref "J4") (pin "1") (pinfunction "1_1") (pintype "passive"))
      (node (ref "JP2") (pin "1") (pinfunction "1_1") (pintype "passive"))
      (node (ref "R11") (pin "2") (pinfunction "2_2") (pintype "passive"))
      (node (ref "R12") (pin "2") (pinfunction "2_2") (pintype "passive"))
      (node (ref "R13") (pin "2") (pinfunction "2_2") (pintype "passive"))
      (node (ref "R14") (pin "2") (pinfunction "2_2") (pintype "passive"))
      (node (ref "R17") (pin "2") (pinfunction "2_2") (pintype "passive"))
      (node (ref "R18") (pin "2") (pinfunction "2_2") (pintype "passive"))
      (node (ref "R19") (pin "2") (pinfunction "2_2") (pintype "passive"))
      (node (ref "R4") (pin "1") (pinfunction "1_1") (pintype "passive"))
      (node (ref "R5") (pin "1") (pinfunction "1_1") (pintype "passive"))
      (node (ref "TP4") (pin "TP") (pinfunction "TP_TP") (pintype "input"))
      (node (ref "U1") (pin "18") (pinfunction "AVCC_18") (pintype "bidirectional"))
      (node (ref "U1") (pin "4") (pinfunction "VCC_4") (pintype "bidirectional"))
      (node (ref "U1") (pin "6") (pinfunction "VCC_6") (pintype "bidirectional"))
    )
    (net (code "2") (name "+5V") (class "Default")
      (node (ref "F2") (pin "P$2") (pinfunction "P$2_P$2") (pintype "bidirectional"))
      (node (ref "L3") (pin "1") (pinfunction "1_1") (pintype "passive"))
    )
    (net (code "3") (name "5VIN") (class "Default")
      (node (ref "F2") (pin "P$1") (pinfunction "P$1_P$1") (pintype "bidirectional"))
      (node (ref "J3") (pin "1") (pinfunction "1_1") (pintype "passive"))
      (node (ref "Q8") (pin "1") (pinfunction "G_1") (pintype "passive"))
    )
    (net (code "4") (name "10MHZ_IN") (class "Default")
      (node (ref "C40") (pin "1") (pinfunction "1_1") (pintype "passive"))
      (node (ref "J7") (pin "1") (pinfunction "1_1") (pintype "passive"))
    )
    (net (code "5") (name "10MHZ_PLL") (class "Default")
      (node (ref "C25") (pin "1") (pinfunction "1_1") (pintype "passive"))
      (node (ref "IC3") (pin "3") (pinfunction "Y0_3") (pintype "bidirectional"))
      (node (ref "R9") (pin "2") (pinfunction "2_2") (pintype "passive"))
    )
    (net (code "6") (name "10MHZ_RPI") (class "Default")
      (node (ref "IC3") (pin "5") (pinfunction "Y2_5") (pintype "bidirectional"))
      (node (ref "J3") (pin "10") (pinfunction "10_10") (pintype "passive"))
    )
    (net (code "7") (name "10MHZ_USRP") (class "Default")
      (node (ref "IC3") (pin "8") (pinfunction "Y1_8") (pintype "bidirectional"))
      (node (ref "J2") (pin "1") (pinfunction "1_1") (pintype "passive"))
    )
    (net (code "8") (name "A0") (class "Default")
      (node (ref "J4") (pin "5") (pinfunction "5_5") (pintype "passive"))
      (node (ref "U1") (pin "23") (pinfunction "PC0(ADC0)_23") (pintype "bidirectional"))
    )
    (net (code "9") (name "A1") (class "Default")
      (node (ref "J4") (pin "8") (pinfunction "8_8") (pintype "passive"))
      (node (ref "U1") (pin "24") (pinfunction "PC1(ADC1)_24") (pintype "bidirectional"))
    )
    (net (code "10") (name "A2") (class "Default")
      (node (ref "J4") (pin "6") (pinfunction "6_6") (pintype "passive"))
      (node (ref "U1") (pin "25") (pinfunction "PC2(ADC2)_25") (pintype "bidirectional"))
    )
    (net (code "11") (name "A3") (class "Default")
      (node (ref "J4") (pin "4") (pinfunction "4_4") (pintype "passive"))
      (node (ref "U1") (pin "26") (pinfunction "PC3(ADC3)_26") (pintype "bidirectional"))
    )
    (net (code "12") (name "A6") (class "Default")
      (node (ref "J4") (pin "7") (pinfunction "7_7") (pintype "passive"))
      (node (ref "U1") (pin "19") (pinfunction "ADC6_19") (pintype "bidirectional"))
    )
    (net (code "13") (name "A7") (class "Default")
      (node (ref "J4") (pin "3") (pinfunction "3_3") (pintype "passive"))
      (node (ref "U1") (pin "22") (pinfunction "ADC7_22") (pintype "bidirectional"))
    )
    (net (code "14") (name "CE") (class "Default")
      (node (ref "R13") (pin "1") (pinfunction "1_1") (pintype "passive"))
      (node (ref "R2") (pin "4") (pinfunction "1_4") (pintype "passive"))
      (node (ref "U1") (pin "13") (pinfunction "PB1(OC1A)_13") (pintype "bidirectional"))
    )
    (net (code "15") (name "CLK") (class "Default")
      (node (ref "R2") (pin "1") (pinfunction "1_1") (pintype "passive"))
      (node (ref "TP2") (pin "TP") (pinfunction "TP_TP") (pintype "input"))
      (node (ref "U1") (pin "17") (pinfunction "PB5(SCK)_17") (pintype "bidirectional"))
    )
    (net (code "16") (name "CP") (class "Default")
      (node (ref "C23") (pin "1") (pinfunction "1_1") (pintype "passive"))
      (node (ref "C24") (pin "1") (pinfunction "1_1") (pintype "passive"))
      (node (ref "IC1") (pin "7") (pinfunction "CP_OUT_7") (pintype "bidirectional"))
      (node (ref "R6") (pin "2") (pinfunction "2_2") (pintype "passive"))
    )
    (net (code "17") (name "D0") (class "Default")
      (node (ref "J3") (pin "2") (pinfunction "2_2") (pintype "passive"))
      (node (ref "U1") (pin "30") (pinfunction "PD0(RXD)_30") (pintype "bidirectional"))
    )
    (net (code "18") (name "D1") (class "Default")
      (node (ref "J3") (pin "3") (pinfunction "3_3") (pintype "passive"))
      (node (ref "U1") (pin "31") (pinfunction "PD1(TXD)_31") (pintype "bidirectional"))
    )
    (net (code "19") (name "D2") (class "Default")
      (node (ref "IC7") (pin "4") (pinfunction "Y_4") (pintype "bidirectional"))
      (node (ref "U1") (pin "32") (pinfunction "PD2(INT0)_32") (pintype "bidirectional"))
    )
    (net (code "20") (name "D3") (class "Default")
      (node (ref "U1") (pin "1") (pinfunction "PD3(INT1)_1") (pintype "bidirectional"))
    )
    (net (code "21") (name "D4") (class "Default")
      (node (ref "U1") (pin "2") (pinfunction "PD4(XCK/T0)_2") (pintype "bidirectional"))
    )
    (net (code "22") (name "D5") (class "Default")
      (node (ref "U1") (pin "9") (pinfunction "PD5(T1)_9") (pintype "bidirectional"))
    )
    (net (code "23") (name "D6") (class "Default")
      (node (ref "R20") (pin "2") (pinfunction "2_2") (pintype "passive"))
      (node (ref "U1") (pin "10") (pinfunction "PD6(AIN0)_10") (pintype "bidirectional"))
    )
    (net (code "24") (name "GND") (class "Default")
      (node (ref "C1") (pin "2") (pinfunction "2_2") (pintype "passive"))
      (node (ref "C10") (pin "2") (pinfunction "2_2") (pintype "passive"))
      (node (ref "C11") (pin "2") (pinfunction "2_2") (pintype "passive"))
      (node (ref "C12") (pin "2") (pinfunction "2_2") (pintype "passive"))
      (node (ref "C13") (pin "2") (pinfunction "2_2") (pintype "passive"))
      (node (ref "C14") (pin "2") (pinfunction "2_2") (pintype "passive"))
      (node (ref "C15") (pin "2") (pinfunction "2_2") (pintype "passive"))
      (node (ref "C16") (pin "2") (pinfunction "2_2") (pintype "passive"))
      (node (ref "C19") (pin "1") (pinfunction "1_1") (pintype "passive"))
      (node (ref "C2") (pin "2") (pinfunction "2_2") (pintype "passive"))
      (node (ref "C20") (pin "1") (pinfunction "1_1") (pintype "passive"))
      (node (ref "C22") (pin "2") (pinfunction "2_2") (pintype "passive"))
      (node (ref "C24") (pin "2") (pinfunction "2_2") (pintype "passive"))
      (node (ref "C26") (pin "1") (pinfunction "1_1") (pintype "passive"))
      (node (ref "C27") (pin "1") (pinfunction "1_1") (pintype "passive"))
      (node (ref "C28") (pin "1") (pinfunction "1_1") (pintype "passive"))
      (node (ref "C29") (pin "1") (pinfunction "1_1") (pintype "passive"))
      (node (ref "C3") (pin "2") (pinfunction "2_2") (pintype "passive"))
      (node (ref "C30") (pin "2") (pinfunction "2_2") (pintype "passive"))
      (node (ref "C31") (pin "2") (pinfunction "2_2") (pintype "passive"))
      (node (ref "C32") (pin "2") (pinfunction "2_2") (pintype "passive"))
      (node (ref "C33") (pin "2") (pinfunction "2_2") (pintype "passive"))
      (node (ref "C34") (pin "2") (pinfunction "2_2") (pintype "passive"))
      (node (ref "C35") (pin "2") (pinfunction "2_2") (pintype "passive"))
      (node (ref "C36") (pin "2") (pinfunction "2_2") (pintype "passive"))
      (node (ref "C37") (pin "2") (pinfunction "2_2") (pintype "passive"))
      (node (ref "C38") (pin "2") (pinfunction "2_2") (pintype "passive"))
      (node (ref "C39") (pin "2") (pinfunction "2_2") (pintype "passive"))
      (node (ref "C4") (pin "2") (pinfunction "2_2") (pintype "passive"))
      (node (ref "C41") (pin "2") (pinfunction "2_2") (pintype "passive"))
      (node (ref "C42") (pin "2") (pinfunction "2_2") (pintype "passive"))
      (node (ref "C43") (pin "2") (pinfunction "2_2") (pintype "passive"))
      (node (ref "C5") (pin "2") (pinfunction "2_2") (pintype "passive"))
      (node (ref "C6") (pin "2") (pinfunction "2_2") (pintype "passive"))
      (node (ref "C7") (pin "2") (pinfunction "2_2") (pintype "passive"))
      (node (ref "C8") (pin "2") (pinfunction "2_2") (pintype "passive"))
      (node (ref "C9") (pin "2") (pinfunction "2_2") (pintype "passive"))
      (node (ref "FL1") (pin "1") (pinfunction "GND_1_1") (pintype "bidirectional"))
      (node (ref "FL1") (pin "3") (pinfunction "GND_1_3") (pintype "bidirectional"))
      (node (ref "FL1") (pin "5") (pinfunction "NC_5") (pintype "bidirectional"))
      (node (ref "IC1") (pin "11") (pinfunction "GND_RF_11") (pintype "bidirectional"))
      (node (ref "IC1") (pin "18") (pinfunction "GND_VCO_18") (pintype "bidirectional"))
      (node (ref "IC1") (pin "21") (pinfunction "GND_TUNE_21") (pintype "bidirectional"))
      (node (ref "IC1") (pin "27") (pinfunction "GND_DIG_27") (pintype "bidirectional"))
      (node (ref "IC1") (pin "31") (pinfunction "GND_SD_31") (pintype "bidirectional"))
      (node (ref "IC1") (pin "33") (pinfunction "EP_33") (pintype "bidirectional"))
      (node (ref "IC1") (pin "8") (pinfunction "GND_CP_8") (pintype "bidirectional"))
      (node (ref "IC1") (pin "9") (pinfunction "GND_PLL_9") (pintype "bidirectional"))
      (node (ref "IC2") (pin "4") (pinfunction "GND_4") (pintype "bidirectional"))
      (node (ref "IC3") (pin "4") (pinfunction "GND_4") (pintype "bidirectional"))
      (node (ref "IC4") (pin "5") (pinfunction "GND_5") (pintype "bidirectional"))
      (node (ref "IC5") (pin "5") (pinfunction "GND_5") (pintype "bidirectional"))
      (node (ref "IC5") (pin "7") (pinfunction "EP_7") (pintype "bidirectional"))
      (node (ref "IC6") (pin "1") (pinfunction "GND_1_1") (pintype "bidirectional"))
      (node (ref "IC6") (pin "2") (pinfunction "GND_2_2") (pintype "bidirectional"))
      (node (ref "IC7") (pin "1") (pinfunction "B_1") (pintype "bidirectional"))
      (node (ref "IC7") (pin "2") (pinfunction "GND_2") (pintype "bidirectional"))
      (node (ref "IC7") (pin "6") (pinfunction "C_6") (pintype "bidirectional"))
      (node (ref "J1") (pin "10") (pinfunction "2_10") (pintype "passive"))
      (node (ref "J1") (pin "2") (pinfunction "2_2") (pintype "passive"))
      (node (ref "J1") (pin "3") (pinfunction "2_3") (pintype "passive"))
      (node (ref "J1") (pin "4") (pinfunction "2_4") (pintype "passive"))
      (node (ref "J1") (pin "5") (pinfunction "2_5") (pintype "passive"))
      (node (ref "J1") (pin "7") (pinfunction "2_7") (pintype "passive"))
      (node (ref "J1") (pin "8") (pinfunction "2_8") (pintype "passive"))
      (node (ref "J1") (pin "9") (pinfunction "2_9") (pintype "passive"))
      (node (ref "J2") (pin "10") (pinfunction "2_10") (pintype "passive"))
      (node (ref "J2") (pin "2") (pinfunction "2_2") (pintype "passive"))
      (node (ref "J2") (pin "3") (pinfunction "2_3") (pintype "passive"))
      (node (ref "J2") (pin "4") (pinfunction "2_4") (pintype "passive"))
      (node (ref "J2") (pin "5") (pinfunction "2_5") (pintype "passive"))
      (node (ref "J2") (pin "7") (pinfunction "2_7") (pintype "passive"))
      (node (ref "J2") (pin "8") (pinfunction "2_8") (pintype "passive"))
      (node (ref "J2") (pin "9") (pinfunction "2_9") (pintype "passive"))
      (node (ref "J4") (pin "10") (pinfunction "10_10") (pintype "passive"))
      (node (ref "J4") (pin "2") (pinfunction "2_2") (pintype "passive"))
      (node (ref "J4") (pin "9") (pinfunction "9_9") (pintype "passive"))
      (node (ref "J5") (pin "2") (pinfunction "2_2") (pintype "passive"))
      (node (ref "J5") (pin "3") (pinfunction "2_3") (pintype "passive"))
      (node (ref "J5") (pin "4") (pinfunction "2_4") (pintype "passive"))
      (node (ref "J5") (pin "5") (pinfunction "2_5") (pintype "passive"))
      (node (ref "J6") (pin "10") (pinfunction "2_10") (pintype "passive"))
      (node (ref "J6") (pin "2") (pinfunction "2_2") (pintype "passive"))
      (node (ref "J6") (pin "3") (pinfunction "2_3") (pintype "passive"))
      (node (ref "J6") (pin "4") (pinfunction "2_4") (pintype "passive"))
      (node (ref "J6") (pin "5") (pinfunction "2_5") (pintype "passive"))
      (node (ref "J6") (pin "7") (pinfunction "2_7") (pintype "passive"))
      (node (ref "J6") (pin "8") (pinfunction "2_8") (pintype "passive"))
      (node (ref "J6") (pin "9") (pinfunction "2_9") (pintype "passive"))
      (node (ref "J7") (pin "10") (pinfunction "2_10") (pintype "passive"))
      (node (ref "J7") (pin "2") (pinfunction "2_2") (pintype "passive"))
      (node (ref "J7") (pin "3") (pinfunction "2_3") (pintype "passive"))
      (node (ref "J7") (pin "4") (pinfunction "2_4") (pintype "passive"))
      (node (ref "J7") (pin "5") (pinfunction "2_5") (pintype "passive"))
      (node (ref "J7") (pin "7") (pinfunction "2_7") (pintype "passive"))
      (node (ref "J7") (pin "8") (pinfunction "2_8") (pintype "passive"))
      (node (ref "J7") (pin "9") (pinfunction "2_9") (pintype "passive"))
      (node (ref "LED1") (pin "C") (pinfunction "C_C") (pintype "passive"))
      (node (ref "Q8") (pin "2") (pinfunction "S_2") (pintype "passive"))
      (node (ref "R1") (pin "2") (pinfunction "2_2") (pintype "passive"))
      (node (ref "R10") (pin "1") (pinfunction "1_1") (pintype "passive"))
      (node (ref "R23") (pin "1") (pinfunction "1_1") (pintype "passive"))
      (node (ref "R8") (pin "1") (pinfunction "1_1") (pintype "passive"))
      (node (ref "R9") (pin "1") (pinfunction "1_1") (pintype "passive"))
      (node (ref "TP6") (pin "TP") (pinfunction "TP_TP") (pintype "input"))
      (node (ref "U1") (pin "21") (pinfunction "AGND_21") (pintype "bidirectional"))
      (node (ref "U1") (pin "3") (pinfunction "GND_3") (pintype "bidirectional"))
      (node (ref "U1") (pin "5") (pinfunction "GND_5") (pintype "bidirectional"))
      (node (ref "Y1") (pin "2") (pinfunction "GND_1_2") (pintype "bidirectional"))
      (node (ref "Y1") (pin "4") (pinfunction "GND_1_4") (pintype "bidirectional"))
    )
    (net (code "25") (name "GNDIN") (class "Default")
      (node (ref "J3") (pin "6") (pinfunction "6_6") (pintype "passive"))
      (node (ref "J3") (pin "8") (pinfunction "8_8") (pintype "passive"))
      (node (ref "J3") (pin "9") (pinfunction "9_9") (pintype "passive"))
      (node (ref "Q8") (pin "3") (pinfunction "D_3") (pintype "passive"))
    )
    (net (code "26") (name "LD") (class "Default")
      (node (ref "IC1") (pin "25") (pinfunction "LD_25") (pintype "bidirectional"))
      (node (ref "U1") (pin "12") (pinfunction "PB0(ICP)_12") (pintype "bidirectional"))
    )
    (net (code "27") (name "LE") (class "Default")
      (node (ref "R14") (pin "1") (pinfunction "1_1") (pintype "passive"))
      (node (ref "R2") (pin "3") (pinfunction "1_3") (pintype "passive"))
      (node (ref "U1") (pin "14") (pinfunction "PB2(SS/OC1B)_14") (pintype "bidirectional"))
    )
    (net (code "28") (name "MISO") (class "Default")
      (node (ref "JP1") (pin "1") (pinfunction "1_1") (pintype "passive"))
      (node (ref "TP1") (pin "TP") (pinfunction "TP_TP") (pintype "input"))
      (node (ref "U1") (pin "16") (pinfunction "PB4(MISO)_16") (pintype "bidirectional"))
    )
    (net (code "29") (name "MOSI") (class "Default")
      (node (ref "R2") (pin "2") (pinfunction "1_2") (pintype "passive"))
      (node (ref "TP5") (pin "TP") (pinfunction "TP_TP") (pintype "input"))
      (node (ref "U1") (pin "15") (pinfunction "PB3(MOSI/OC2)_15") (pintype "bidirectional"))
    )
    (net (code "30") (name "MUX_OUT") (class "Default")
      (node (ref "IC1") (pin "30") (pinfunction "MUX_OUT_30") (pintype "bidirectional"))
      (node (ref "JP1") (pin "2") (pinfunction "2_2") (pintype "passive"))
    )
    (net (code "31") (name "Net-(C23-Pad2)") (class "Default")
      (node (ref "C23") (pin "2") (pinfunction "2_2") (pintype "passive"))
      (node (ref "R7") (pin "2") (pinfunction "2_2") (pintype "passive"))
    )
    (net (code "32") (name "Net-(FL1-BALANCED_PORT_1)") (class "Default")
      (node (ref "C18") (pin "2") (pinfunction "2_2") (pintype "passive"))
      (node (ref "FL1") (pin "4") (pinfunction "BALANCED_PORT_1_4") (pintype "bidirectional"))
    )
    (net (code "33") (name "Net-(FL1-BALANCED_PORT_2)") (class "Default")
      (node (ref "C17") (pin "2") (pinfunction "2_2") (pintype "passive"))
      (node (ref "FL1") (pin "6") (pinfunction "BALANCED_PORT_2_6") (pintype "bidirectional"))
    )
    (net (code "34") (name "Net-(FL1-UNBALANCED)") (class "Default")
      (node (ref "C21") (pin "1") (pinfunction "1_1") (pintype "passive"))
      (node (ref "FL1") (pin "2") (pinfunction "UNBALANCED_2") (pintype "bidirectional"))
    )
    (net (code "35") (name "Net-(IC1-BIAS_FILT)") (class "Default")
      (node (ref "C3") (pin "1") (pinfunction "1_1") (pintype "passive"))
      (node (ref "C4") (pin "1") (pinfunction "1_1") (pintype "passive"))
      (node (ref "IC1") (pin "23") (pinfunction "BIAS_FILT_23") (pintype "bidirectional"))
    )
    (net (code "36") (name "Net-(IC1-CE)") (class "Default")
      (node (ref "IC1") (pin "4") (pinfunction "CE_4") (pintype "bidirectional"))
      (node (ref "R2") (pin "5") (pinfunction "2_5") (pintype "passive"))
    )
    (net (code "37") (name "Net-(IC1-CLK)") (class "Default")
      (node (ref "IC1") (pin "1") (pinfunction "CLK_1") (pintype "bidirectional"))
      (node (ref "R2") (pin "8") (pinfunction "2_8") (pintype "passive"))
    )
    (net (code "38") (name "Net-(IC1-DATA)") (class "Default")
      (node (ref "IC1") (pin "2") (pinfunction "DATA_2") (pintype "bidirectional"))
      (node (ref "R2") (pin "7") (pinfunction "2_7") (pintype "passive"))
    )
    (net (code "39") (name "Net-(IC1-LE)") (class "Default")
      (node (ref "IC1") (pin "3") (pinfunction "LE_3") (pintype "bidirectional"))
      (node (ref "R2") (pin "6") (pinfunction "2_6") (pintype "passive"))
    )
    (net (code "40") (name "Net-(IC1-NOISE_FILT)") (class "Default")
      (node (ref "C1") (pin "1") (pinfunction "1_1") (pintype "passive"))
      (node (ref "C2") (pin "1") (pinfunction "1_1") (pintype "passive"))
      (node (ref "IC1") (pin "19") (pinfunction "NOISE_FILT_19") (pintype "bidirectional"))
    )
    (net (code "41") (name "Net-(IC1-REF_IN)") (class "Default")
      (node (ref "C25") (pin "2") (pinfunction "2_2") (pintype "passive"))
      (node (ref "IC1") (pin "29") (pinfunction "REF_IN_29") (pintype "bidirectional"))
      (node (ref "R10") (pin "2") (pinfunction "2_2") (pintype "passive"))
      (node (ref "R11") (pin "1") (pinfunction "1_1") (pintype "passive"))
    )
    (net (code "42") (name "Net-(IC1-REG)") (class "Default")
      (node (ref "C5") (pin "1") (pinfunction "1_1") (pintype "passive"))
      (node (ref "C6") (pin "1") (pinfunction "1_1") (pintype "passive"))
      (node (ref "IC1") (pin "24") (pinfunction "REG_24") (pintype "bidirectional"))
    )
    (net (code "43") (name "Net-(IC1-RFOUTA_N)") (class "Default")
      (node (ref "C18") (pin "1") (pinfunction "1_1") (pintype "passive"))
      (node (ref "IC1") (pin "13") (pinfunction "RFOUTA_N_13") (pintype "bidirectional"))
      (node (ref "R5") (pin "2") (pinfunction "2_2") (pintype "passive"))
    )
    (net (code "44") (name "Net-(IC1-RFOUTA_P)") (class "Default")
      (node (ref "C17") (pin "1") (pinfunction "1_1") (pintype "passive"))
      (node (ref "IC1") (pin "12") (pinfunction "RFOUTA_P_12") (pintype "bidirectional"))
      (node (ref "R4") (pin "2") (pinfunction "2_2") (pintype "passive"))
    )
    (net (code "45") (name "Net-(IC1-RFOUT_EN)") (class "Default")
      (node (ref "IC1") (pin "26") (pinfunction "RFOUT_EN_26") (pintype "bidirectional"))
      (node (ref "R21") (pin "2") (pinfunction "2_2") (pintype "passive"))
    )
    (net (code "46") (name "Net-(IC1-RSET)") (class "Default")
      (node (ref "IC1") (pin "22") (pinfunction "RSET_22") (pintype "bidirectional"))
      (node (ref "R1") (pin "1") (pinfunction "1_1") (pintype "passive"))
    )
    (net (code "47") (name "Net-(IC1-TUNE)") (class "Default")
      (node (ref "C22") (pin "1") (pinfunction "1_1") (pintype "passive"))
      (node (ref "IC1") (pin "20") (pinfunction "TUNE_20") (pintype "bidirectional"))
      (node (ref "R6") (pin "1") (pinfunction "1_1") (pintype "passive"))
    )
    (net (code "48") (name "Net-(IC2-1G)") (class "Default")
      (node (ref "IC2") (pin "2") (pinfunction "1G_2") (pintype "bidirectional"))
      (node (ref "R16") (pin "1") (pinfunction "1_1") (pintype "passive"))
    )
    (net (code "49") (name "Net-(IC2-VDD)") (class "Default")
      (node (ref "C34") (pin "1") (pinfunction "1_1") (pintype "passive"))
      (node (ref "C35") (pin "1") (pinfunction "1_1") (pintype "passive"))
      (node (ref "IC2") (pin "6") (pinfunction "VDD_6") (pintype "bidirectional"))
      (node (ref "L1") (pin "2") (pinfunction "2_2") (pintype "passive"))
      (node (ref "R16") (pin "2") (pinfunction "2_2") (pintype "passive"))
    )
    (net (code "50") (name "Net-(IC3-1G)") (class "Default")
      (node (ref "IC3") (pin "2") (pinfunction "1G_2") (pintype "bidirectional"))
      (node (ref "R15") (pin "1") (pinfunction "1_1") (pintype "passive"))
    )
    (net (code "51") (name "Net-(IC3-CLKIN)") (class "Default")
      (node (ref "C40") (pin "2") (pinfunction "2_2") (pintype "passive"))
      (node (ref "IC3") (pin "1") (pinfunction "CLKIN_1") (pintype "bidirectional"))
      (node (ref "R23") (pin "2") (pinfunction "2_2") (pintype "passive"))
      (node (ref "R24") (pin "1") (pinfunction "1_1") (pintype "passive"))
    )
    (net (code "52") (name "Net-(IC3-VDD)") (class "Default")
      (node (ref "C31") (pin "1") (pinfunction "1_1") (pintype "passive"))
      (node (ref "C32") (pin "1") (pinfunction "1_1") (pintype "passive"))
      (node (ref "IC3") (pin "6") (pinfunction "VDD_6") (pintype "bidirectional"))
      (node (ref "L2") (pin "2") (pinfunction "2_2") (pintype "passive"))
      (node (ref "R15") (pin "2") (pinfunction "2_2") (pintype "passive"))
    )
    (net (code "53") (name "Net-(IC4-EN)") (class "Default")
      (node (ref "C36") (pin "1") (pinfunction "1_1") (pintype "passive"))
      (node (ref "C38") (pin "1") (pinfunction "1_1") (pintype "passive"))
      (node (ref "IC4") (pin "4") (pinfunction "EN_4") (pintype "bidirectional"))
      (node (ref "IC4") (pin "6") (pinfunction "IN_6") (pintype "bidirectional"))
      (node (ref "L3") (pin "2") (pinfunction "2_2") (pintype "passive"))
    )
    (net (code "54") (name "Net-(IC4-PG)") (class "Default")
      (node (ref "IC4") (pin "3") (pinfunction "PG_3") (pintype "bidirectional"))
      (node (ref "R19") (pin "1") (pinfunction "1_1") (pintype "passive"))
    )
    (net (code "55") (name "Net-(IC5-PG)") (class "Default")
      (node (ref "IC5") (pin "3") (pinfunction "PG_3") (pintype "bidirectional"))
      (node (ref "R3") (pin "1") (pinfunction "1_1") (pintype "passive"))
    )
    (net (code "56") (name "Net-(IC6-VREF)") (class "Default")
      (node (ref "C43") (pin "1") (pinfunction "1_1") (pintype "passive"))
      (node (ref "IC6") (pin "6") (pinfunction "VREF_6") (pintype "bidirectional"))
      (node (ref "R24") (pin "2") (pinfunction "2_2") (pintype "passive"))
    )
    (net (code "57") (name "Net-(LED1-PadA)") (class "Default")
      (node (ref "LED1") (pin "A") (pinfunction "A_A") (pintype "passive"))
      (node (ref "R20") (pin "1") (pinfunction "1_1") (pintype "passive"))
    )
    (net (code "58") (name "Net-(U1-PB6(XTAL1{slash}TOSC1))") (class "Default")
      (node (ref "C26") (pin "2") (pinfunction "2_2") (pintype "passive"))
      (node (ref "U1") (pin "7") (pinfunction "PB6(XTAL1/TOSC1)_7") (pintype "bidirectional"))
      (node (ref "Y1") (pin "3") (pinfunction "X2_3") (pintype "bidirectional"))
    )
    (net (code "59") (name "Net-(U1-PB7(XTAL2{slash}TOSC2))") (class "Default")
      (node (ref "C27") (pin "2") (pinfunction "2_2") (pintype "passive"))
      (node (ref "U1") (pin "8") (pinfunction "PB7(XTAL2/TOSC2)_8") (pintype "bidirectional"))
      (node (ref "Y1") (pin "1") (pinfunction "X1_1") (pintype "bidirectional"))
    )
    (net (code "60") (name "PPS_IN") (class "Default")
      (node (ref "IC2") (pin "1") (pinfunction "CLKIN_1") (pintype "bidirectional"))
      (node (ref "J6") (pin "1") (pinfunction "1_1") (pintype "passive"))
    )
    (net (code "61") (name "PPS_PLL") (class "Default")
      (node (ref "IC2") (pin "3") (pinfunction "Y0_3") (pintype "bidirectional"))
      (node (ref "JP1") (pin "3") (pinfunction "3_3") (pintype "passive"))
    )
    (net (code "62") (name "PPS_RPI") (class "Default")
      (node (ref "IC2") (pin "5") (pinfunction "Y2_5") (pintype "bidirectional"))
      (node (ref "IC7") (pin "3") (pinfunction "A_3") (pintype "bidirectional"))
      (node (ref "J3") (pin "7") (pinfunction "7_7") (pintype "passive"))
    )
    (net (code "63") (name "PPS_USRP") (class "Default")
      (node (ref "IC2") (pin "8") (pinfunction "Y1_8") (pintype "bidirectional"))
      (node (ref "J1") (pin "1") (pinfunction "1_1") (pintype "passive"))
    )
    (net (code "64") (name "RESET") (class "Default")
      (node (ref "R12") (pin "1") (pinfunction "1_1") (pintype "passive"))
      (node (ref "TP3") (pin "TP") (pinfunction "TP_TP") (pintype "input"))
      (node (ref "U1") (pin "29") (pinfunction "PC6(/RESET)_29") (pintype "bidirectional"))
    )
    (net (code "65") (name "RFOUT_EN") (class "Default")
      (node (ref "R21") (pin "1") (pinfunction "1_1") (pintype "passive"))
      (node (ref "U1") (pin "11") (pinfunction "PD7(AIN1)_11") (pintype "bidirectional"))
    )
    (net (code "66") (name "RF_OUT") (class "Default")
      (node (ref "C21") (pin "2") (pinfunction "2_2") (pintype "passive"))
      (node (ref "J5") (pin "1") (pinfunction "1_1") (pintype "passive"))
    )
    (net (code "67") (name "SCL") (class "Default")
      (node (ref "J3") (pin "5") (pinfunction "5_5") (pintype "passive"))
      (node (ref "R18") (pin "1") (pinfunction "1_1") (pintype "passive"))
      (node (ref "U1") (pin "28") (pinfunction "PC5(ADC5/SCL)_28") (pintype "bidirectional"))
    )
    (net (code "68") (name "SDA") (class "Default")
      (node (ref "J3") (pin "4") (pinfunction "4_4") (pintype "passive"))
      (node (ref "R17") (pin "1") (pinfunction "1_1") (pintype "passive"))
      (node (ref "U1") (pin "27") (pinfunction "PC4(ADC4/SDA)_27") (pintype "bidirectional"))
    )
    (net (code "69") (name "SW") (class "Default")
      (node (ref "IC1") (pin "5") (pinfunction "SW_5") (pintype "bidirectional"))
      (node (ref "R7") (pin "1") (pinfunction "1_1") (pintype "passive"))
      (node (ref "R8") (pin "2") (pinfunction "2_2") (pintype "passive"))
    )
    (net (code "70") (name "V_BUFFER") (class "Default")
      (node (ref "C30") (pin "1") (pinfunction "1_1") (pintype "passive"))
      (node (ref "C33") (pin "1") (pinfunction "1_1") (pintype "passive"))
      (node (ref "IC5") (pin "1") (pinfunction "OUT_1") (pintype "bidirectional"))
      (node (ref "JP2") (pin "2") (pinfunction "2_2") (pintype "passive"))
      (node (ref "L1") (pin "1") (pinfunction "1_1") (pintype "passive"))
      (node (ref "L2") (pin "1") (pinfunction "1_1") (pintype "passive"))
      (node (ref "R3") (pin "2") (pinfunction "2_2") (pintype "passive"))
    )
    (net (code "71") (name "unconnected-(IC1-RFOUTB_N-Pad15)") (class "Default")
      (node (ref "IC1") (pin "15") (pinfunction "RFOUTB_N_15") (pintype "bidirectional"))
    )
    (net (code "72") (name "unconnected-(IC1-RFOUTB_P-Pad14)") (class "Default")
      (node (ref "IC1") (pin "14") (pinfunction "RFOUTB_P_14") (pintype "bidirectional"))
    )
    (net (code "73") (name "unconnected-(IC2-NC-Pad7)") (class "Default")
      (node (ref "IC2") (pin "7") (pinfunction "NC_7") (pintype "no_connect"))
    )
    (net (code "74") (name "unconnected-(IC3-NC-Pad7)") (class "Default")
      (node (ref "IC3") (pin "7") (pinfunction "NC_7") (pintype "no_connect"))
    )
    (net (code "75") (name "unconnected-(IC4-EP-Pad7)") (class "Default")
      (node (ref "IC4") (pin "7") (pinfunction "EP_7") (pintype "bidirectional"))
    )
    (net (code "76") (name "unconnected-(IC4-NC-Pad2)") (class "Default")
      (node (ref "IC4") (pin "2") (pinfunction "NC_2") (pintype "no_connect"))
    )
    (net (code "77") (name "unconnected-(IC5-NC-Pad2)") (class "Default")
      (node (ref "IC5") (pin "2") (pinfunction "NC_2") (pintype "no_connect"))
    )
    (net (code "78") (name "unconnected-(IC6-NR-Pad5)") (class "Default")
      (node (ref "IC6") (pin "5") (pinfunction "NR_5") (pintype "bidirectional"))
    )
    (net (code "79") (name "unconnected-(U1-AREF-Pad20)") (class "Default")
      (node (ref "U1") (pin "20") (pinfunction "AREF_20") (pintype "bidirectional"))
    )
  )
)
